# M8350.net
KiCad netlist of a schematic drawn in EAGLE
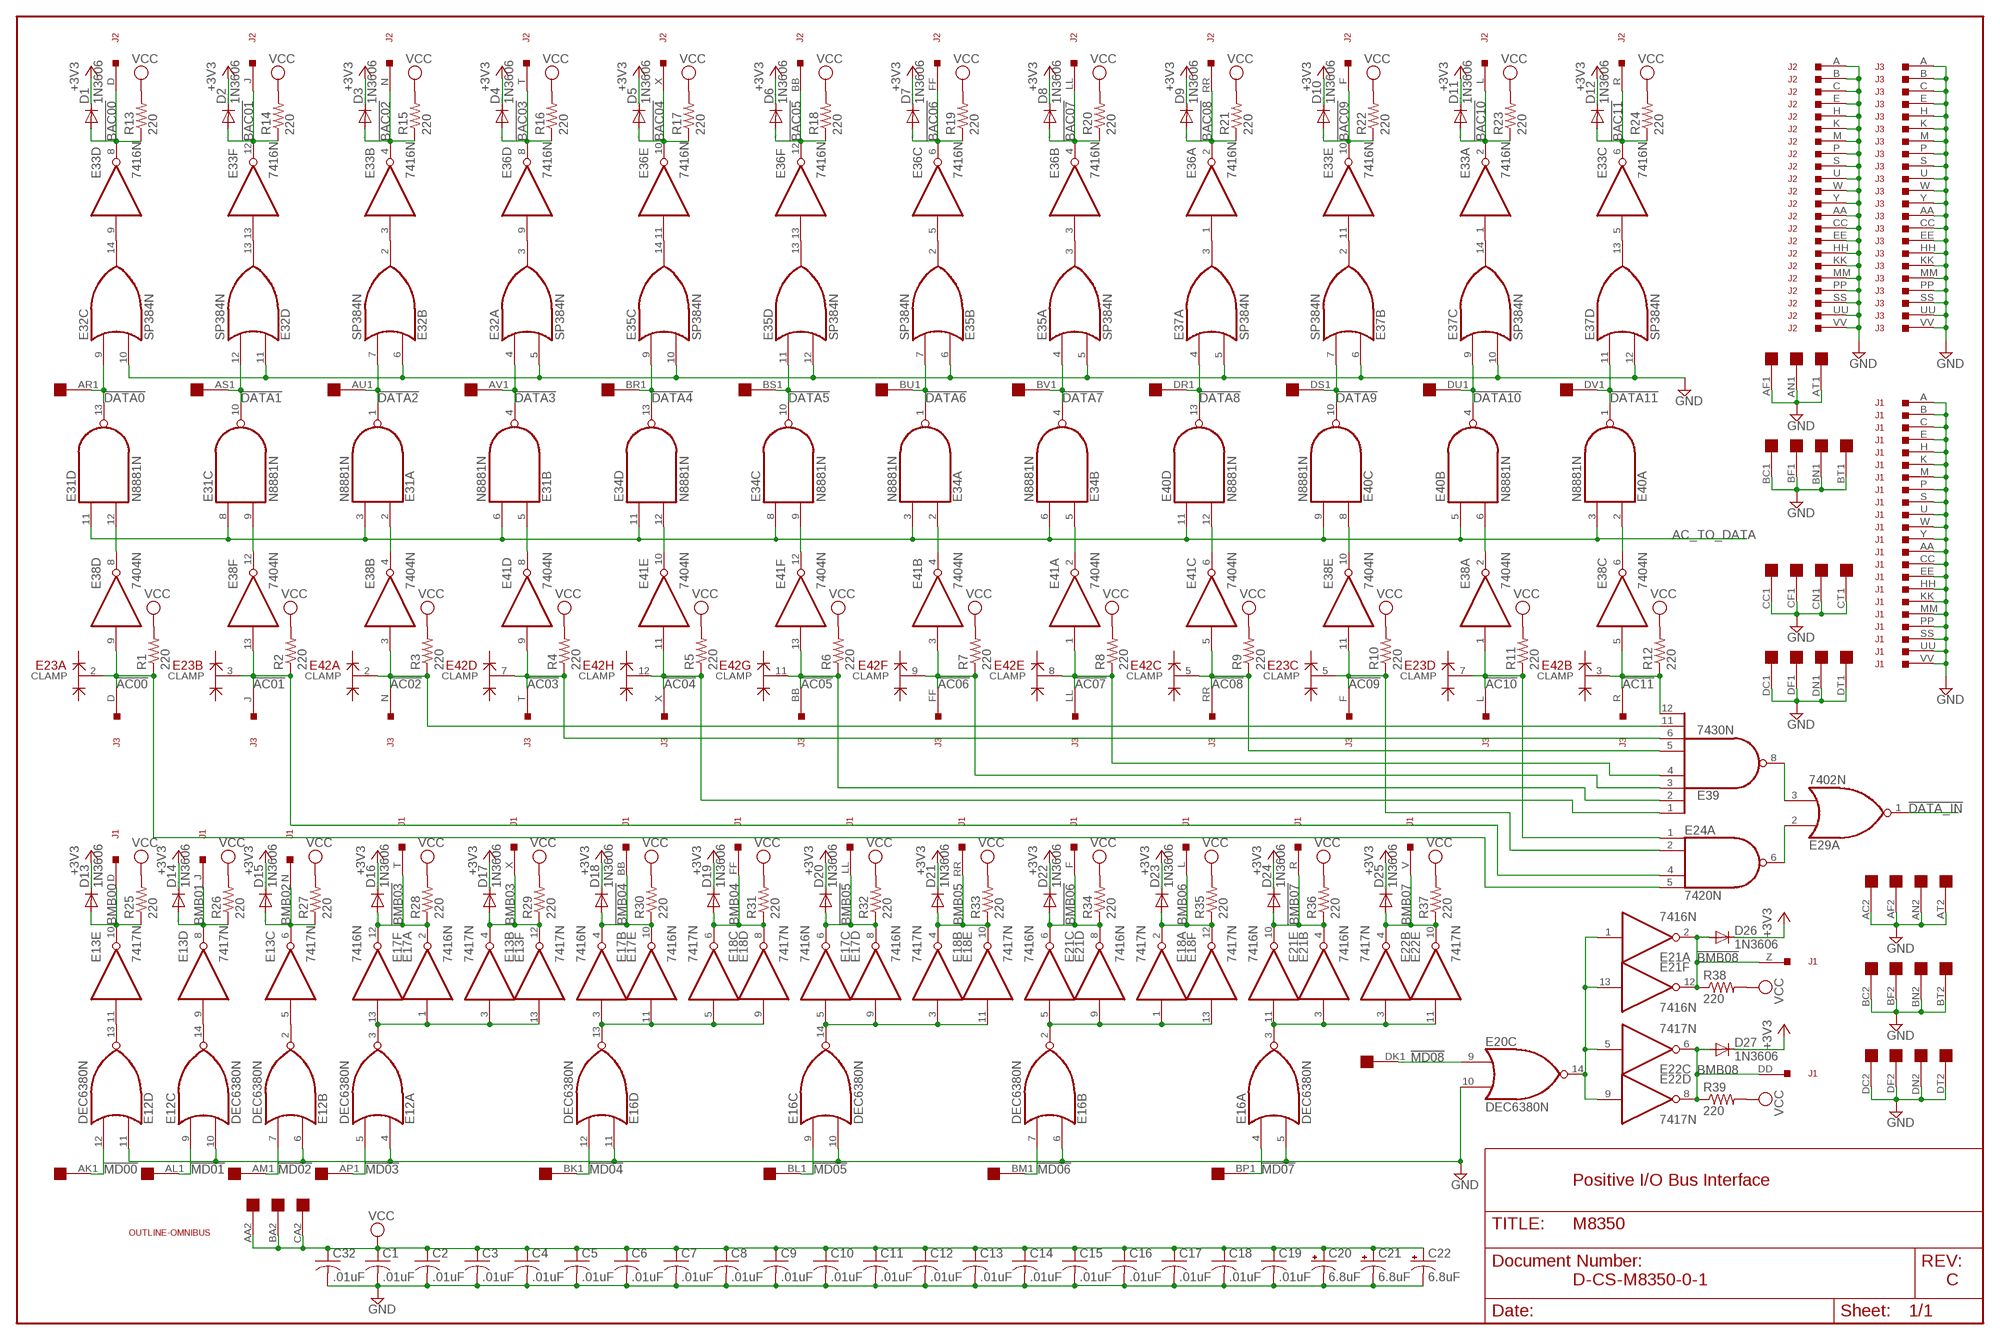
[diagram p0: schematic, sheet 1, part 1 of 2]
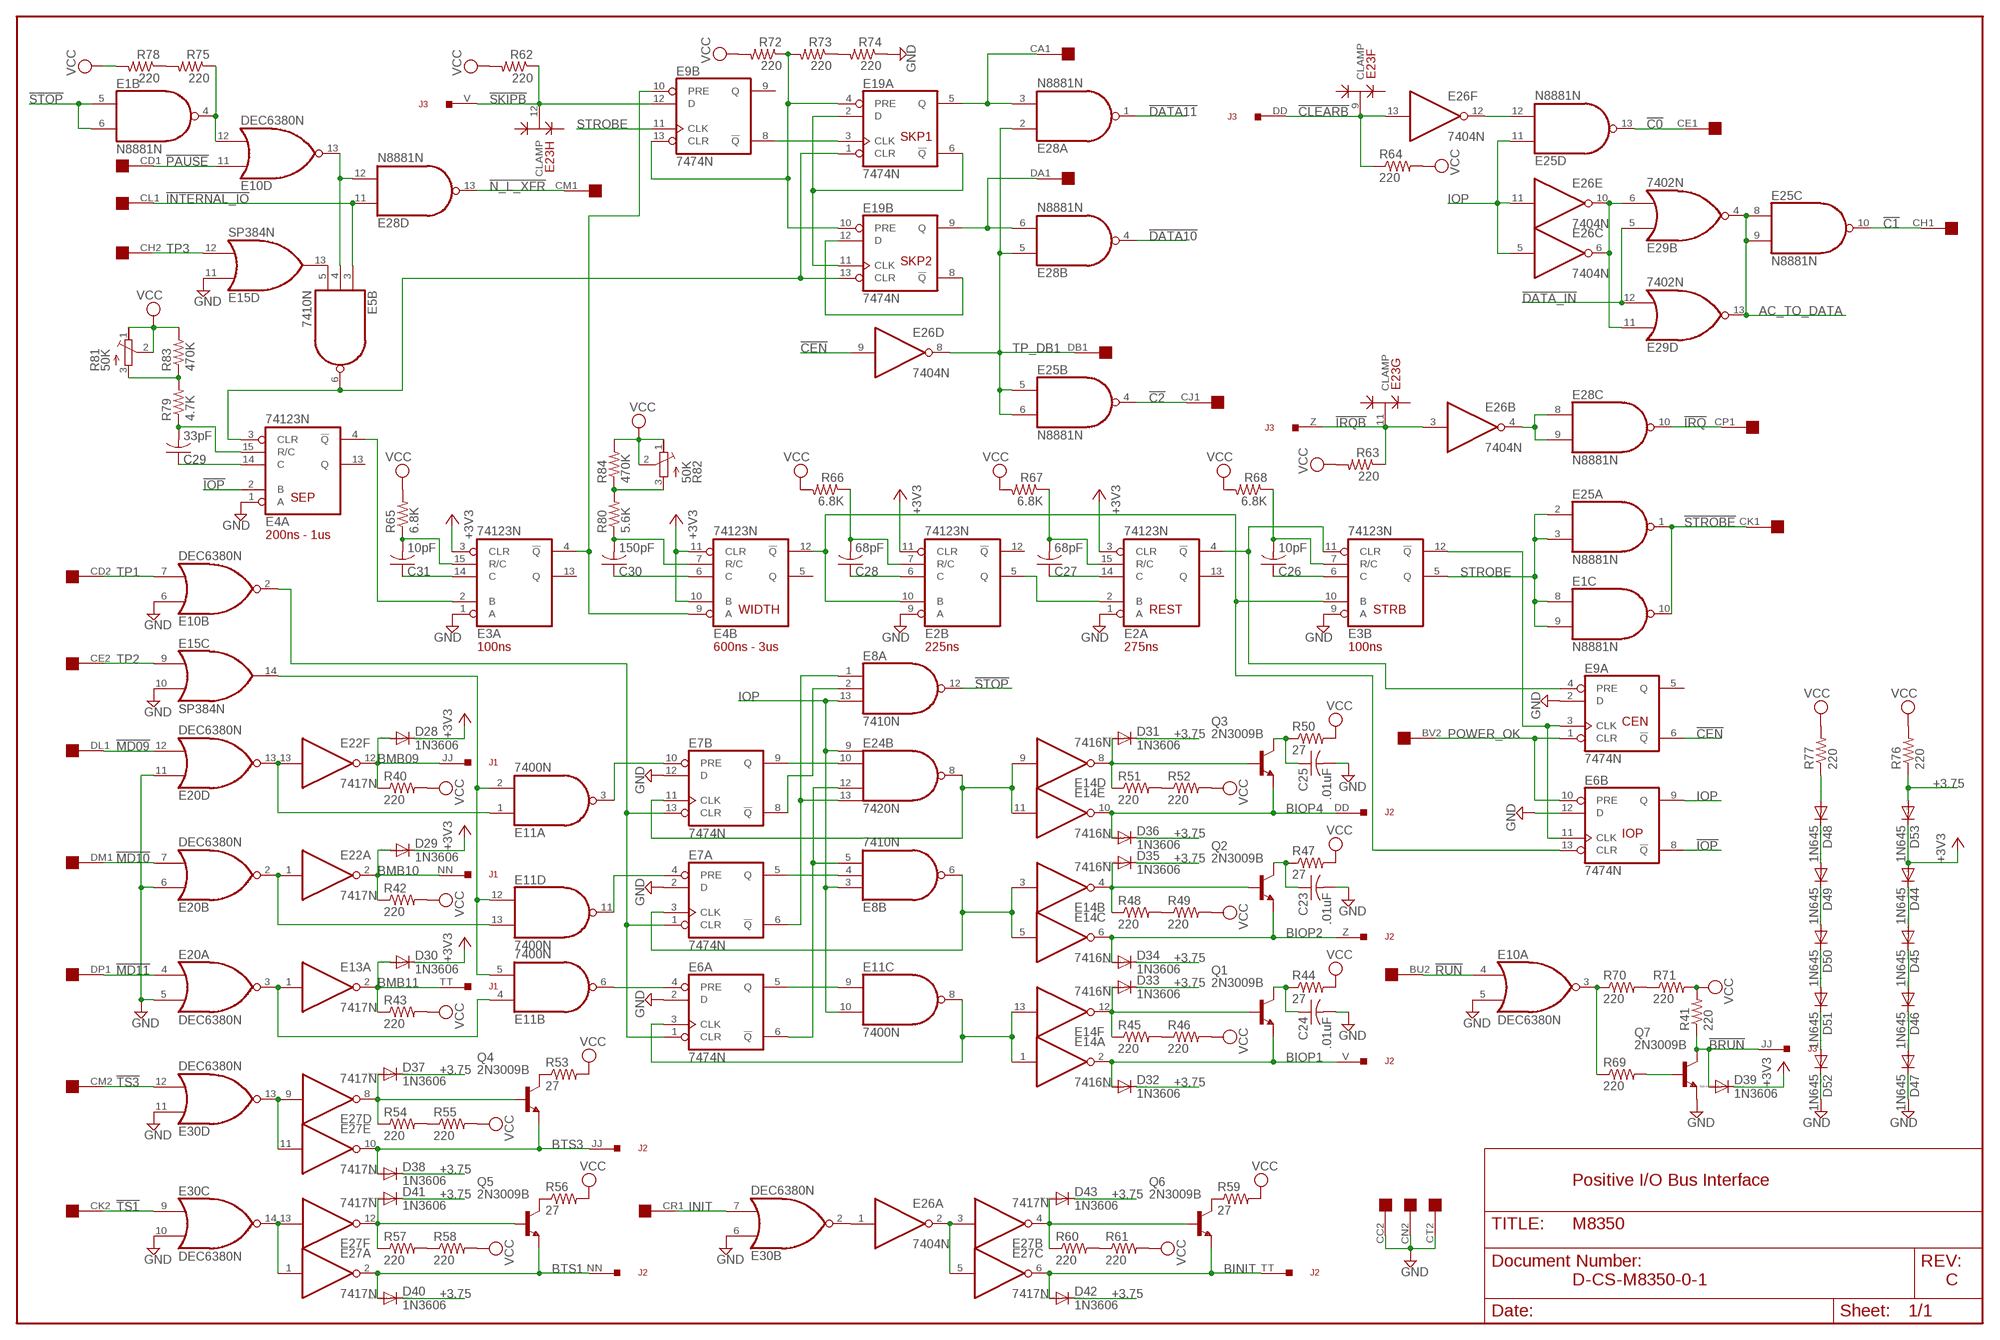
[diagram p1: schematic, sheet 1, part 2 of 2]

(export (version "E")
  (design (tool "Eeschema 10.0.6"))
  (components
    (comp (ref "C1")
      (value ".01uF")
      (footprint "eagle-import:C050-025X075")
      (libsource (lib "eagle-import") (part "C-US050-025X075"))
    )
    (comp (ref "C2")
      (value ".01uF")
      (footprint "eagle-import:C050-025X075")
      (libsource (lib "eagle-import") (part "C-US050-025X075"))
    )
    (comp (ref "C3")
      (value ".01uF")
      (footprint "eagle-import:C050-025X075")
      (libsource (lib "eagle-import") (part "C-US050-025X075"))
    )
    (comp (ref "C4")
      (value ".01uF")
      (footprint "eagle-import:C050-025X075")
      (libsource (lib "eagle-import") (part "C-US050-025X075"))
    )
    (comp (ref "C5")
      (value ".01uF")
      (footprint "eagle-import:C050-025X075")
      (libsource (lib "eagle-import") (part "C-US050-025X075"))
    )
    (comp (ref "C6")
      (value ".01uF")
      (footprint "eagle-import:C050-025X075")
      (libsource (lib "eagle-import") (part "C-US050-025X075"))
    )
    (comp (ref "C7")
      (value ".01uF")
      (footprint "eagle-import:C050-025X075")
      (libsource (lib "eagle-import") (part "C-US050-025X075"))
    )
    (comp (ref "C8")
      (value ".01uF")
      (footprint "eagle-import:C050-025X075")
      (libsource (lib "eagle-import") (part "C-US050-025X075"))
    )
    (comp (ref "C9")
      (value ".01uF")
      (footprint "eagle-import:C050-025X075")
      (libsource (lib "eagle-import") (part "C-US050-025X075"))
    )
    (comp (ref "C10")
      (value ".01uF")
      (footprint "eagle-import:C050-025X075")
      (libsource (lib "eagle-import") (part "C-US050-025X075"))
    )
    (comp (ref "C11")
      (value ".01uF")
      (footprint "eagle-import:C050-025X075")
      (libsource (lib "eagle-import") (part "C-US050-025X075"))
    )
    (comp (ref "C12")
      (value ".01uF")
      (footprint "eagle-import:C050-025X075")
      (libsource (lib "eagle-import") (part "C-US050-025X075"))
    )
    (comp (ref "C13")
      (value ".01uF")
      (footprint "eagle-import:C050-025X075")
      (libsource (lib "eagle-import") (part "C-US050-025X075"))
    )
    (comp (ref "C14")
      (value ".01uF")
      (footprint "eagle-import:C050-025X075")
      (libsource (lib "eagle-import") (part "C-US050-025X075"))
    )
    (comp (ref "C15")
      (value ".01uF")
      (footprint "eagle-import:C050-025X075")
      (libsource (lib "eagle-import") (part "C-US050-025X075"))
    )
    (comp (ref "C16")
      (value ".01uF")
      (footprint "eagle-import:C050-025X075")
      (libsource (lib "eagle-import") (part "C-US050-025X075"))
    )
    (comp (ref "C17")
      (value ".01uF")
      (footprint "eagle-import:C050-025X075")
      (libsource (lib "eagle-import") (part "C-US050-025X075"))
    )
    (comp (ref "C18")
      (value ".01uF")
      (footprint "eagle-import:C050-025X075")
      (libsource (lib "eagle-import") (part "C-US050-025X075"))
    )
    (comp (ref "C19")
      (value ".01uF")
      (footprint "eagle-import:C050-025X075")
      (libsource (lib "eagle-import") (part "C-US050-025X075"))
    )
    (comp (ref "C20")
      (value "6.8uF")
      (footprint "eagle-import:E12-8")
      (libsource (lib "eagle-import") (part "CPOL-USE20-8AXIAL"))
    )
    (comp (ref "C21")
      (value "6.8uF")
      (footprint "eagle-import:E12-8")
      (libsource (lib "eagle-import") (part "CPOL-USE20-8AXIAL"))
    )
    (comp (ref "C22")
      (value "6.8uF")
      (footprint "eagle-import:E12-8")
      (libsource (lib "eagle-import") (part "CPOL-USE20-8AXIAL"))
    )
    (comp (ref "C23")
      (value ".01uF")
      (footprint "eagle-import:C050-025X075")
      (libsource (lib "eagle-import") (part "C-US050-025X075"))
    )
    (comp (ref "C24")
      (value ".01uF")
      (footprint "eagle-import:C050-025X075")
      (libsource (lib "eagle-import") (part "C-US050-025X075"))
    )
    (comp (ref "C25")
      (value ".01uF")
      (footprint "eagle-import:C050-025X075")
      (libsource (lib "eagle-import") (part "C-US050-025X075"))
    )
    (comp (ref "C26")
      (value "10pF")
      (footprint "eagle-import:C050-025X075")
      (libsource (lib "eagle-import") (part "C-US050-025X075"))
    )
    (comp (ref "C27")
      (value "68pF")
      (footprint "eagle-import:C050-025X075")
      (libsource (lib "eagle-import") (part "C-US050-025X075"))
    )
    (comp (ref "C28")
      (value "68pF")
      (footprint "eagle-import:C050-025X075")
      (libsource (lib "eagle-import") (part "C-US050-025X075"))
    )
    (comp (ref "C29")
      (value "33pF")
      (footprint "eagle-import:C050-025X075")
      (libsource (lib "eagle-import") (part "C-US050-025X075"))
    )
    (comp (ref "C30")
      (value "150pF")
      (footprint "eagle-import:C050-025X075")
      (libsource (lib "eagle-import") (part "C-US050-025X075"))
    )
    (comp (ref "C31")
      (value "10pF")
      (footprint "eagle-import:C050-025X075")
      (libsource (lib "eagle-import") (part "C-US050-025X075"))
    )
    (comp (ref "C32")
      (value ".01uF")
      (footprint "eagle-import:C050-025X075")
      (libsource (lib "eagle-import") (part "C-US050-025X075"))
    )
    (comp (ref "D1")
      (value "1N3606")
      (footprint "eagle-import:DO35-10")
      (libsource (lib "eagle-import") (part "DIODE-DO35-10"))
    )
    (comp (ref "D2")
      (value "1N3606")
      (footprint "eagle-import:DO35-10")
      (libsource (lib "eagle-import") (part "DIODE-DO35-10"))
    )
    (comp (ref "D3")
      (value "1N3606")
      (footprint "eagle-import:DO35-10")
      (libsource (lib "eagle-import") (part "DIODE-DO35-10"))
    )
    (comp (ref "D4")
      (value "1N3606")
      (footprint "eagle-import:DO35-10")
      (libsource (lib "eagle-import") (part "DIODE-DO35-10"))
    )
    (comp (ref "D5")
      (value "1N3606")
      (footprint "eagle-import:DO35-10")
      (libsource (lib "eagle-import") (part "DIODE-DO35-10"))
    )
    (comp (ref "D6")
      (value "1N3606")
      (footprint "eagle-import:DO35-10")
      (libsource (lib "eagle-import") (part "DIODE-DO35-10"))
    )
    (comp (ref "D7")
      (value "1N3606")
      (footprint "eagle-import:DO35-10")
      (libsource (lib "eagle-import") (part "DIODE-DO35-10"))
    )
    (comp (ref "D8")
      (value "1N3606")
      (footprint "eagle-import:DO35-10")
      (libsource (lib "eagle-import") (part "DIODE-DO35-10"))
    )
    (comp (ref "D9")
      (value "1N3606")
      (footprint "eagle-import:DO35-10")
      (libsource (lib "eagle-import") (part "DIODE-DO35-10"))
    )
    (comp (ref "D10")
      (value "1N3606")
      (footprint "eagle-import:DO35-10")
      (libsource (lib "eagle-import") (part "DIODE-DO35-10"))
    )
    (comp (ref "D11")
      (value "1N3606")
      (footprint "eagle-import:DO35-10")
      (libsource (lib "eagle-import") (part "DIODE-DO35-10"))
    )
    (comp (ref "D12")
      (value "1N3606")
      (footprint "eagle-import:DO35-10")
      (libsource (lib "eagle-import") (part "DIODE-DO35-10"))
    )
    (comp (ref "D13")
      (value "1N3606")
      (footprint "eagle-import:DO35-10")
      (libsource (lib "eagle-import") (part "DIODE-DO35-10"))
    )
    (comp (ref "D14")
      (value "1N3606")
      (footprint "eagle-import:DO35-10")
      (libsource (lib "eagle-import") (part "DIODE-DO35-10"))
    )
    (comp (ref "D15")
      (value "1N3606")
      (footprint "eagle-import:DO35-10")
      (libsource (lib "eagle-import") (part "DIODE-DO35-10"))
    )
    (comp (ref "D16")
      (value "1N3606")
      (footprint "eagle-import:DO35-10")
      (libsource (lib "eagle-import") (part "DIODE-DO35-10"))
    )
    (comp (ref "D17")
      (value "1N3606")
      (footprint "eagle-import:DO35-10")
      (libsource (lib "eagle-import") (part "DIODE-DO35-10"))
    )
    (comp (ref "D18")
      (value "1N3606")
      (footprint "eagle-import:DO35-10")
      (libsource (lib "eagle-import") (part "DIODE-DO35-10"))
    )
    (comp (ref "D19")
      (value "1N3606")
      (footprint "eagle-import:DO35-10")
      (libsource (lib "eagle-import") (part "DIODE-DO35-10"))
    )
    (comp (ref "D20")
      (value "1N3606")
      (footprint "eagle-import:DO35-10")
      (libsource (lib "eagle-import") (part "DIODE-DO35-10"))
    )
    (comp (ref "D21")
      (value "1N3606")
      (footprint "eagle-import:DO35-10")
      (libsource (lib "eagle-import") (part "DIODE-DO35-10"))
    )
    (comp (ref "D22")
      (value "1N3606")
      (footprint "eagle-import:DO35-10")
      (libsource (lib "eagle-import") (part "DIODE-DO35-10"))
    )
    (comp (ref "D23")
      (value "1N3606")
      (footprint "eagle-import:DO35-10")
      (libsource (lib "eagle-import") (part "DIODE-DO35-10"))
    )
    (comp (ref "D24")
      (value "1N3606")
      (footprint "eagle-import:DO35-10")
      (libsource (lib "eagle-import") (part "DIODE-DO35-10"))
    )
    (comp (ref "D25")
      (value "1N3606")
      (footprint "eagle-import:DO35-10")
      (libsource (lib "eagle-import") (part "DIODE-DO35-10"))
    )
    (comp (ref "D26")
      (value "1N3606")
      (footprint "eagle-import:DO35-10")
      (libsource (lib "eagle-import") (part "DIODE-DO35-10"))
    )
    (comp (ref "D27")
      (value "1N3606")
      (footprint "eagle-import:DO35-10")
      (libsource (lib "eagle-import") (part "DIODE-DO35-10"))
    )
    (comp (ref "D28")
      (value "1N3606")
      (footprint "eagle-import:DO35-10")
      (libsource (lib "eagle-import") (part "DIODE-DO35-10"))
    )
    (comp (ref "D29")
      (value "1N3606")
      (footprint "eagle-import:DO35-10")
      (libsource (lib "eagle-import") (part "DIODE-DO35-10"))
    )
    (comp (ref "D30")
      (value "1N3606")
      (footprint "eagle-import:DO35-10")
      (libsource (lib "eagle-import") (part "DIODE-DO35-10"))
    )
    (comp (ref "D31")
      (value "1N3606")
      (footprint "eagle-import:DO35-10")
      (libsource (lib "eagle-import") (part "DIODE-DO35-10"))
    )
    (comp (ref "D32")
      (value "1N3606")
      (footprint "eagle-import:DO35-10")
      (libsource (lib "eagle-import") (part "DIODE-DO35-10"))
    )
    (comp (ref "D33")
      (value "1N3606")
      (footprint "eagle-import:DO35-10")
      (libsource (lib "eagle-import") (part "DIODE-DO35-10"))
    )
    (comp (ref "D34")
      (value "1N3606")
      (footprint "eagle-import:DO35-10")
      (libsource (lib "eagle-import") (part "DIODE-DO35-10"))
    )
    (comp (ref "D35")
      (value "1N3606")
      (footprint "eagle-import:DO35-10")
      (libsource (lib "eagle-import") (part "DIODE-DO35-10"))
    )
    (comp (ref "D36")
      (value "1N3606")
      (footprint "eagle-import:DO35-10")
      (libsource (lib "eagle-import") (part "DIODE-DO35-10"))
    )
    (comp (ref "D37")
      (value "1N3606")
      (footprint "eagle-import:DO35-10")
      (libsource (lib "eagle-import") (part "DIODE-DO35-10"))
    )
    (comp (ref "D38")
      (value "1N3606")
      (footprint "eagle-import:DO35-10")
      (libsource (lib "eagle-import") (part "DIODE-DO35-10"))
    )
    (comp (ref "D39")
      (value "1N3606")
      (footprint "eagle-import:DO35-10")
      (libsource (lib "eagle-import") (part "DIODE-DO35-10"))
    )
    (comp (ref "D40")
      (value "1N3606")
      (footprint "eagle-import:DO35-10")
      (libsource (lib "eagle-import") (part "DIODE-DO35-10"))
    )
    (comp (ref "D41")
      (value "1N3606")
      (footprint "eagle-import:DO35-10")
      (libsource (lib "eagle-import") (part "DIODE-DO35-10"))
    )
    (comp (ref "D42")
      (value "1N3606")
      (footprint "eagle-import:DO35-10")
      (libsource (lib "eagle-import") (part "DIODE-DO35-10"))
    )
    (comp (ref "D43")
      (value "1N3606")
      (footprint "eagle-import:DO35-10")
      (libsource (lib "eagle-import") (part "DIODE-DO35-10"))
    )
    (comp (ref "D44")
      (value "1N645")
      (footprint "eagle-import:DO35-10")
      (libsource (lib "eagle-import") (part "DIODE-DO35-10"))
    )
    (comp (ref "D45")
      (value "1N645")
      (footprint "eagle-import:DO35-10")
      (libsource (lib "eagle-import") (part "DIODE-DO35-10"))
    )
    (comp (ref "D46")
      (value "1N645")
      (footprint "eagle-import:DO35-10")
      (libsource (lib "eagle-import") (part "DIODE-DO35-10"))
    )
    (comp (ref "D47")
      (value "1N645")
      (footprint "eagle-import:DO35-10")
      (libsource (lib "eagle-import") (part "DIODE-DO35-10"))
    )
    (comp (ref "D48")
      (value "1N645")
      (footprint "eagle-import:DO35-10")
      (libsource (lib "eagle-import") (part "DIODE-DO35-10"))
    )
    (comp (ref "D49")
      (value "1N645")
      (footprint "eagle-import:DO35-10")
      (libsource (lib "eagle-import") (part "DIODE-DO35-10"))
    )
    (comp (ref "D50")
      (value "1N645")
      (footprint "eagle-import:DO35-10")
      (libsource (lib "eagle-import") (part "DIODE-DO35-10"))
    )
    (comp (ref "D51")
      (value "1N645")
      (footprint "eagle-import:DO35-10")
      (libsource (lib "eagle-import") (part "DIODE-DO35-10"))
    )
    (comp (ref "D52")
      (value "1N645")
      (footprint "eagle-import:DO35-10")
      (libsource (lib "eagle-import") (part "DIODE-DO35-10"))
    )
    (comp (ref "D53")
      (value "1N645")
      (footprint "eagle-import:DO35-10")
      (libsource (lib "eagle-import") (part "DIODE-DO35-10"))
    )
    (comp (ref "E1")
      (value "N8881N")
      (footprint "eagle-import:DIL14")
      (libsource (lib "eagle-import") (part "N8881N"))
    )
    (comp (ref "E2")
      (value "74123N")
      (footprint "eagle-import:DIL16")
      (libsource (lib "eagle-import") (part "74123N"))
    )
    (comp (ref "E3")
      (value "74123N")
      (footprint "eagle-import:DIL16")
      (libsource (lib "eagle-import") (part "74123N"))
    )
    (comp (ref "E4")
      (value "74123N")
      (footprint "eagle-import:DIL16")
      (libsource (lib "eagle-import") (part "74123N"))
    )
    (comp (ref "E5")
      (value "7410N")
      (footprint "eagle-import:DIL14")
      (libsource (lib "eagle-import") (part "7410N"))
    )
    (comp (ref "E6")
      (value "7474N")
      (footprint "eagle-import:DIL14")
      (libsource (lib "eagle-import") (part "7474NS"))
    )
    (comp (ref "E7")
      (value "7474N")
      (footprint "eagle-import:DIL14")
      (libsource (lib "eagle-import") (part "7474NS"))
    )
    (comp (ref "E8")
      (value "7410N")
      (footprint "eagle-import:DIL14")
      (libsource (lib "eagle-import") (part "7410N"))
    )
    (comp (ref "E9")
      (value "7474N")
      (footprint "eagle-import:DIL14")
      (libsource (lib "eagle-import") (part "7474NS"))
    )
    (comp (ref "E10")
      (value "DEC6380N")
      (footprint "eagle-import:DIL14")
      (libsource (lib "eagle-import") (part "SP380N"))
    )
    (comp (ref "E11")
      (value "7400N")
      (footprint "eagle-import:DIL14")
      (libsource (lib "eagle-import") (part "7400N"))
    )
    (comp (ref "E12")
      (value "DEC6380N")
      (footprint "eagle-import:DIL14")
      (libsource (lib "eagle-import") (part "SP380N"))
    )
    (comp (ref "E13")
      (value "7417N")
      (footprint "eagle-import:DIL14")
      (libsource (lib "eagle-import") (part "7417N"))
    )
    (comp (ref "E14")
      (value "7416N")
      (footprint "eagle-import:DIL14")
      (libsource (lib "eagle-import") (part "7416N"))
    )
    (comp (ref "E15")
      (value "SP384N")
      (footprint "eagle-import:DIL14")
      (libsource (lib "eagle-import") (part "SP384N"))
    )
    (comp (ref "E16")
      (value "DEC6380N")
      (footprint "eagle-import:DIL14")
      (libsource (lib "eagle-import") (part "SP380N"))
    )
    (comp (ref "E17")
      (value "7416N")
      (footprint "eagle-import:DIL14")
      (libsource (lib "eagle-import") (part "7416N"))
    )
    (comp (ref "E18")
      (value "7417N")
      (footprint "eagle-import:DIL14")
      (libsource (lib "eagle-import") (part "7417N"))
    )
    (comp (ref "E19")
      (value "7474N")
      (footprint "eagle-import:DIL14")
      (libsource (lib "eagle-import") (part "7474NS"))
    )
    (comp (ref "E20")
      (value "DEC6380N")
      (footprint "eagle-import:DIL14")
      (libsource (lib "eagle-import") (part "SP380N"))
    )
    (comp (ref "E21")
      (value "7416N")
      (footprint "eagle-import:DIL14")
      (libsource (lib "eagle-import") (part "7416N"))
    )
    (comp (ref "E22")
      (value "7417N")
      (footprint "eagle-import:DIL14")
      (libsource (lib "eagle-import") (part "7417N"))
    )
    (comp (ref "E23")
      (value "DEC2501")
      (footprint "eagle-import:DIL14")
      (libsource (lib "eagle-import") (part "DEC2501"))
    )
    (comp (ref "E24")
      (value "7420N")
      (footprint "eagle-import:DIL14")
      (libsource (lib "eagle-import") (part "7420NS"))
    )
    (comp (ref "E25")
      (value "N8881N")
      (footprint "eagle-import:DIL14")
      (libsource (lib "eagle-import") (part "N8881N"))
    )
    (comp (ref "E26")
      (value "7404N")
      (footprint "eagle-import:DIL14")
      (libsource (lib "eagle-import") (part "7404N"))
    )
    (comp (ref "E27")
      (value "7417N")
      (footprint "eagle-import:DIL14")
      (libsource (lib "eagle-import") (part "7417N"))
    )
    (comp (ref "E28")
      (value "N8881N")
      (footprint "eagle-import:DIL14")
      (libsource (lib "eagle-import") (part "N8881N"))
    )
    (comp (ref "E29")
      (value "7402N")
      (footprint "eagle-import:DIL14")
      (libsource (lib "eagle-import") (part "7402N"))
    )
    (comp (ref "E30")
      (value "DEC6380N")
      (footprint "eagle-import:DIL14")
      (libsource (lib "eagle-import") (part "SP380N"))
    )
    (comp (ref "E31")
      (value "N8881N")
      (footprint "eagle-import:DIL14")
      (libsource (lib "eagle-import") (part "N8881N"))
    )
    (comp (ref "E32")
      (value "SP384N")
      (footprint "eagle-import:DIL14")
      (libsource (lib "eagle-import") (part "SP384N"))
    )
    (comp (ref "E33")
      (value "7416N")
      (footprint "eagle-import:DIL14")
      (libsource (lib "eagle-import") (part "7416N"))
    )
    (comp (ref "E34")
      (value "N8881N")
      (footprint "eagle-import:DIL14")
      (libsource (lib "eagle-import") (part "N8881N"))
    )
    (comp (ref "E35")
      (value "SP384N")
      (footprint "eagle-import:DIL14")
      (libsource (lib "eagle-import") (part "SP384N"))
    )
    (comp (ref "E36")
      (value "7416N")
      (footprint "eagle-import:DIL14")
      (libsource (lib "eagle-import") (part "7416N"))
    )
    (comp (ref "E37")
      (value "SP384N")
      (footprint "eagle-import:DIL14")
      (libsource (lib "eagle-import") (part "SP384N"))
    )
    (comp (ref "E38")
      (value "7404N")
      (footprint "eagle-import:DIL14")
      (libsource (lib "eagle-import") (part "7404N"))
    )
    (comp (ref "E39")
      (value "7430N")
      (footprint "eagle-import:DIL14")
      (libsource (lib "eagle-import") (part "7430N"))
    )
    (comp (ref "E40")
      (value "N8881N")
      (footprint "eagle-import:DIL14")
      (libsource (lib "eagle-import") (part "N8881N"))
    )
    (comp (ref "E41")
      (value "7404N")
      (footprint "eagle-import:DIL14")
      (libsource (lib "eagle-import") (part "7404N"))
    )
    (comp (ref "E42")
      (value "DEC2501")
      (footprint "eagle-import:DIL14")
      (libsource (lib "eagle-import") (part "DEC2501"))
    )
    (comp (ref "J1")
      (value "DEC40PINSH")
      (footprint "eagle-import:DEC40PINH")
      (libsource (lib "eagle-import") (part "DEC40PINSH"))
    )
    (comp (ref "J2")
      (value "DEC40PINSH")
      (footprint "eagle-import:DEC40PINH")
      (libsource (lib "eagle-import") (part "DEC40PINSH"))
    )
    (comp (ref "J3")
      (value "DEC40PINSH")
      (footprint "eagle-import:DEC40PINH")
      (libsource (lib "eagle-import") (part "DEC40PINSH"))
    )
    (comp (ref "Q1")
      (value "2N3009B")
      (footprint "eagle-import:TO5")
      (libsource (lib "eagle-import") (part "-NPN-TO5"))
    )
    (comp (ref "Q2")
      (value "2N3009B")
      (footprint "eagle-import:TO5")
      (libsource (lib "eagle-import") (part "-NPN-TO5"))
    )
    (comp (ref "Q3")
      (value "2N3009B")
      (footprint "eagle-import:TO5")
      (libsource (lib "eagle-import") (part "-NPN-TO5"))
    )
    (comp (ref "Q4")
      (value "2N3009B")
      (footprint "eagle-import:TO5")
      (libsource (lib "eagle-import") (part "-NPN-TO5"))
    )
    (comp (ref "Q5")
      (value "2N3009B")
      (footprint "eagle-import:TO5")
      (libsource (lib "eagle-import") (part "-NPN-TO5"))
    )
    (comp (ref "Q6")
      (value "2N3009B")
      (footprint "eagle-import:TO5")
      (libsource (lib "eagle-import") (part "-NPN-TO5"))
    )
    (comp (ref "Q7")
      (value "2N3009B")
      (footprint "eagle-import:TO5")
      (libsource (lib "eagle-import") (part "-NPN-TO5"))
    )
    (comp (ref "R1")
      (value "220")
      (footprint "eagle-import:0207_10")
      (libsource (lib "eagle-import") (part "R-US_0207/10"))
    )
    (comp (ref "R2")
      (value "220")
      (footprint "eagle-import:0207_10")
      (libsource (lib "eagle-import") (part "R-US_0207/10"))
    )
    (comp (ref "R3")
      (value "220")
      (footprint "eagle-import:0207_10")
      (libsource (lib "eagle-import") (part "R-US_0207/10"))
    )
    (comp (ref "R4")
      (value "220")
      (footprint "eagle-import:0207_10")
      (libsource (lib "eagle-import") (part "R-US_0207/10"))
    )
    (comp (ref "R5")
      (value "220")
      (footprint "eagle-import:0207_10")
      (libsource (lib "eagle-import") (part "R-US_0207/10"))
    )
    (comp (ref "R6")
      (value "220")
      (footprint "eagle-import:0207_10")
      (libsource (lib "eagle-import") (part "R-US_0207/10"))
    )
    (comp (ref "R7")
      (value "220")
      (footprint "eagle-import:0207_10")
      (libsource (lib "eagle-import") (part "R-US_0207/10"))
    )
    (comp (ref "R8")
      (value "220")
      (footprint "eagle-import:0207_10")
      (libsource (lib "eagle-import") (part "R-US_0207/10"))
    )
    (comp (ref "R9")
      (value "220")
      (footprint "eagle-import:0207_10")
      (libsource (lib "eagle-import") (part "R-US_0207/10"))
    )
    (comp (ref "R10")
      (value "220")
      (footprint "eagle-import:0207_10")
      (libsource (lib "eagle-import") (part "R-US_0207/10"))
    )
    (comp (ref "R11")
      (value "220")
      (footprint "eagle-import:0207_10")
      (libsource (lib "eagle-import") (part "R-US_0207/10"))
    )
    (comp (ref "R12")
      (value "220")
      (footprint "eagle-import:0207_10")
      (libsource (lib "eagle-import") (part "R-US_0207/10"))
    )
    (comp (ref "R13")
      (value "220")
      (footprint "eagle-import:0207_10")
      (libsource (lib "eagle-import") (part "R-US_0207/10"))
    )
    (comp (ref "R14")
      (value "220")
      (footprint "eagle-import:0207_10")
      (libsource (lib "eagle-import") (part "R-US_0207/10"))
    )
    (comp (ref "R15")
      (value "220")
      (footprint "eagle-import:0207_10")
      (libsource (lib "eagle-import") (part "R-US_0207/10"))
    )
    (comp (ref "R16")
      (value "220")
      (footprint "eagle-import:0207_10")
      (libsource (lib "eagle-import") (part "R-US_0207/10"))
    )
    (comp (ref "R17")
      (value "220")
      (footprint "eagle-import:0207_10")
      (libsource (lib "eagle-import") (part "R-US_0207/10"))
    )
    (comp (ref "R18")
      (value "220")
      (footprint "eagle-import:0207_10")
      (libsource (lib "eagle-import") (part "R-US_0207/10"))
    )
    (comp (ref "R19")
      (value "220")
      (footprint "eagle-import:0207_10")
      (libsource (lib "eagle-import") (part "R-US_0207/10"))
    )
    (comp (ref "R20")
      (value "220")
      (footprint "eagle-import:0207_10")
      (libsource (lib "eagle-import") (part "R-US_0207/10"))
    )
    (comp (ref "R21")
      (value "220")
      (footprint "eagle-import:0207_10")
      (libsource (lib "eagle-import") (part "R-US_0207/10"))
    )
    (comp (ref "R22")
      (value "220")
      (footprint "eagle-import:0207_10")
      (libsource (lib "eagle-import") (part "R-US_0207/10"))
    )
    (comp (ref "R23")
      (value "220")
      (footprint "eagle-import:0207_10")
      (libsource (lib "eagle-import") (part "R-US_0207/10"))
    )
    (comp (ref "R24")
      (value "220")
      (footprint "eagle-import:0207_10")
      (libsource (lib "eagle-import") (part "R-US_0207/10"))
    )
    (comp (ref "R25")
      (value "220")
      (footprint "eagle-import:0207_10")
      (libsource (lib "eagle-import") (part "R-US_0207/10"))
    )
    (comp (ref "R26")
      (value "220")
      (footprint "eagle-import:0207_10")
      (libsource (lib "eagle-import") (part "R-US_0207/10"))
    )
    (comp (ref "R27")
      (value "220")
      (footprint "eagle-import:0207_10")
      (libsource (lib "eagle-import") (part "R-US_0207/10"))
    )
    (comp (ref "R28")
      (value "220")
      (footprint "eagle-import:0207_10")
      (libsource (lib "eagle-import") (part "R-US_0207/10"))
    )
    (comp (ref "R29")
      (value "220")
      (footprint "eagle-import:0207_10")
      (libsource (lib "eagle-import") (part "R-US_0207/10"))
    )
    (comp (ref "R30")
      (value "220")
      (footprint "eagle-import:0207_10")
      (libsource (lib "eagle-import") (part "R-US_0207/10"))
    )
    (comp (ref "R31")
      (value "220")
      (footprint "eagle-import:0207_10")
      (libsource (lib "eagle-import") (part "R-US_0207/10"))
    )
    (comp (ref "R32")
      (value "220")
      (footprint "eagle-import:0207_10")
      (libsource (lib "eagle-import") (part "R-US_0207/10"))
    )
    (comp (ref "R33")
      (value "220")
      (footprint "eagle-import:0207_10")
      (libsource (lib "eagle-import") (part "R-US_0207/10"))
    )
    (comp (ref "R34")
      (value "220")
      (footprint "eagle-import:0207_10")
      (libsource (lib "eagle-import") (part "R-US_0207/10"))
    )
    (comp (ref "R35")
      (value "220")
      (footprint "eagle-import:0207_10")
      (libsource (lib "eagle-import") (part "R-US_0207/10"))
    )
    (comp (ref "R36")
      (value "220")
      (footprint "eagle-import:0207_10")
      (libsource (lib "eagle-import") (part "R-US_0207/10"))
    )
    (comp (ref "R37")
      (value "220")
      (footprint "eagle-import:0207_10")
      (libsource (lib "eagle-import") (part "R-US_0207/10"))
    )
    (comp (ref "R38")
      (value "220")
      (footprint "eagle-import:0207_10")
      (libsource (lib "eagle-import") (part "R-US_0207/10"))
    )
    (comp (ref "R39")
      (value "220")
      (footprint "eagle-import:0207_10")
      (libsource (lib "eagle-import") (part "R-US_0207/10"))
    )
    (comp (ref "R40")
      (value "220")
      (footprint "eagle-import:0207_10")
      (libsource (lib "eagle-import") (part "R-US_0207/10"))
    )
    (comp (ref "R41")
      (value "220")
      (footprint "eagle-import:0207_10")
      (libsource (lib "eagle-import") (part "R-US_0207/10"))
    )
    (comp (ref "R42")
      (value "220")
      (footprint "eagle-import:0207_10")
      (libsource (lib "eagle-import") (part "R-US_0207/10"))
    )
    (comp (ref "R43")
      (value "220")
      (footprint "eagle-import:0207_10")
      (libsource (lib "eagle-import") (part "R-US_0207/10"))
    )
    (comp (ref "R44")
      (value "27")
      (footprint "eagle-import:0207_10")
      (libsource (lib "eagle-import") (part "R-US_0207/10"))
    )
    (comp (ref "R45")
      (value "220")
      (footprint "eagle-import:0207_10")
      (libsource (lib "eagle-import") (part "R-US_0207/10"))
    )
    (comp (ref "R46")
      (value "220")
      (footprint "eagle-import:0207_10")
      (libsource (lib "eagle-import") (part "R-US_0207/10"))
    )
    (comp (ref "R47")
      (value "27")
      (footprint "eagle-import:0207_10")
      (libsource (lib "eagle-import") (part "R-US_0207/10"))
    )
    (comp (ref "R48")
      (value "220")
      (footprint "eagle-import:0207_10")
      (libsource (lib "eagle-import") (part "R-US_0207/10"))
    )
    (comp (ref "R49")
      (value "220")
      (footprint "eagle-import:0207_10")
      (libsource (lib "eagle-import") (part "R-US_0207/10"))
    )
    (comp (ref "R50")
      (value "27")
      (footprint "eagle-import:0207_10")
      (libsource (lib "eagle-import") (part "R-US_0207/10"))
    )
    (comp (ref "R51")
      (value "220")
      (footprint "eagle-import:0207_10")
      (libsource (lib "eagle-import") (part "R-US_0207/10"))
    )
    (comp (ref "R52")
      (value "220")
      (footprint "eagle-import:0207_10")
      (libsource (lib "eagle-import") (part "R-US_0207/10"))
    )
    (comp (ref "R53")
      (value "27")
      (footprint "eagle-import:0207_10")
      (libsource (lib "eagle-import") (part "R-US_0207/10"))
    )
    (comp (ref "R54")
      (value "220")
      (footprint "eagle-import:0207_10")
      (libsource (lib "eagle-import") (part "R-US_0207/10"))
    )
    (comp (ref "R55")
      (value "220")
      (footprint "eagle-import:0207_10")
      (libsource (lib "eagle-import") (part "R-US_0207/10"))
    )
    (comp (ref "R56")
      (value "27")
      (footprint "eagle-import:0207_10")
      (libsource (lib "eagle-import") (part "R-US_0207/10"))
    )
    (comp (ref "R57")
      (value "220")
      (footprint "eagle-import:0207_10")
      (libsource (lib "eagle-import") (part "R-US_0207/10"))
    )
    (comp (ref "R58")
      (value "220")
      (footprint "eagle-import:0207_10")
      (libsource (lib "eagle-import") (part "R-US_0207/10"))
    )
    (comp (ref "R59")
      (value "27")
      (footprint "eagle-import:0207_10")
      (libsource (lib "eagle-import") (part "R-US_0207/10"))
    )
    (comp (ref "R60")
      (value "220")
      (footprint "eagle-import:0207_10")
      (libsource (lib "eagle-import") (part "R-US_0207/10"))
    )
    (comp (ref "R61")
      (value "220")
      (footprint "eagle-import:0207_10")
      (libsource (lib "eagle-import") (part "R-US_0207/10"))
    )
    (comp (ref "R62")
      (value "220")
      (footprint "eagle-import:0207_10")
      (libsource (lib "eagle-import") (part "R-US_0207/10"))
    )
    (comp (ref "R63")
      (value "220")
      (footprint "eagle-import:0207_10")
      (libsource (lib "eagle-import") (part "R-US_0207/10"))
    )
    (comp (ref "R64")
      (value "220")
      (footprint "eagle-import:0207_10")
      (libsource (lib "eagle-import") (part "R-US_0207/10"))
    )
    (comp (ref "R65")
      (value "6.8K")
      (footprint "eagle-import:0207_10")
      (libsource (lib "eagle-import") (part "R-US_0207/10"))
    )
    (comp (ref "R66")
      (value "6.8K")
      (footprint "eagle-import:0207_10")
      (libsource (lib "eagle-import") (part "R-US_0207/10"))
    )
    (comp (ref "R67")
      (value "6.8K")
      (footprint "eagle-import:0207_10")
      (libsource (lib "eagle-import") (part "R-US_0207/10"))
    )
    (comp (ref "R68")
      (value "6.8K")
      (footprint "eagle-import:0207_10")
      (libsource (lib "eagle-import") (part "R-US_0207/10"))
    )
    (comp (ref "R69")
      (value "220")
      (footprint "eagle-import:0207_10")
      (libsource (lib "eagle-import") (part "R-US_0207/10"))
    )
    (comp (ref "R70")
      (value "220")
      (footprint "eagle-import:0207_10")
      (libsource (lib "eagle-import") (part "R-US_0207/10"))
    )
    (comp (ref "R71")
      (value "220")
      (footprint "eagle-import:0207_10")
      (libsource (lib "eagle-import") (part "R-US_0207/10"))
    )
    (comp (ref "R72")
      (value "220")
      (footprint "eagle-import:0207_10")
      (libsource (lib "eagle-import") (part "R-US_0207/10"))
    )
    (comp (ref "R73")
      (value "220")
      (footprint "eagle-import:0207_10")
      (libsource (lib "eagle-import") (part "R-US_0207/10"))
    )
    (comp (ref "R74")
      (value "220")
      (footprint "eagle-import:0207_10")
      (libsource (lib "eagle-import") (part "R-US_0207/10"))
    )
    (comp (ref "R75")
      (value "220")
      (footprint "eagle-import:0207_10")
      (libsource (lib "eagle-import") (part "R-US_0207/10"))
    )
    (comp (ref "R76")
      (value "220")
      (footprint "eagle-import:0207_10")
      (libsource (lib "eagle-import") (part "R-US_0207/10"))
    )
    (comp (ref "R77")
      (value "220")
      (footprint "eagle-import:0207_10")
      (libsource (lib "eagle-import") (part "R-US_0207/10"))
    )
    (comp (ref "R78")
      (value "220")
      (footprint "eagle-import:0207_10")
      (libsource (lib "eagle-import") (part "R-US_0207/10"))
    )
    (comp (ref "R79")
      (value "4.7K")
      (footprint "eagle-import:0207_10")
      (libsource (lib "eagle-import") (part "R-US_0207/10"))
    )
    (comp (ref "R80")
      (value "5.6K")
      (footprint "eagle-import:0207_10")
      (libsource (lib "eagle-import") (part "R-US_0207/10"))
    )
    (comp (ref "R81")
      (value "50K")
      (footprint "eagle-import:3006Y")
      (libsource (lib "eagle-import") (part "275P"))
    )
    (comp (ref "R82")
      (value "50K")
      (footprint "eagle-import:3006Y")
      (libsource (lib "eagle-import") (part "275P"))
    )
    (comp (ref "R83")
      (value "470K")
      (footprint "eagle-import:0207_10")
      (libsource (lib "eagle-import") (part "R-US_0207/10"))
    )
    (comp (ref "R84")
      (value "470K")
      (footprint "eagle-import:0207_10")
      (libsource (lib "eagle-import") (part "R-US_0207/10"))
    )
    (comp (ref "U$1")
      (value "OUTLINE-OMNIBUS")
      (footprint "eagle-import:OMNIBUS")
      (libsource (lib "eagle-import") (part "OUTLINE-OMNIBUS"))
    )
    (comp (ref "U$2")
      (value "QUAD")
      (footprint "eagle-import:EDGE-CON8")
      (libsource (lib "eagle-import") (part "QUAD"))
    )
  )
  (nets
    (net (code "1") (name "+3V3") (class "Default")
      (node (ref "D1") (pin "C") (pinfunction "C_C") (pintype "passive"))
      (node (ref "D10") (pin "C") (pinfunction "C_C") (pintype "passive"))
      (node (ref "D11") (pin "C") (pinfunction "C_C") (pintype "passive"))
      (node (ref "D12") (pin "C") (pinfunction "C_C") (pintype "passive"))
      (node (ref "D13") (pin "C") (pinfunction "C_C") (pintype "passive"))
      (node (ref "D14") (pin "C") (pinfunction "C_C") (pintype "passive"))
      (node (ref "D15") (pin "C") (pinfunction "C_C") (pintype "passive"))
      (node (ref "D16") (pin "C") (pinfunction "C_C") (pintype "passive"))
      (node (ref "D17") (pin "C") (pinfunction "C_C") (pintype "passive"))
      (node (ref "D18") (pin "C") (pinfunction "C_C") (pintype "passive"))
      (node (ref "D19") (pin "C") (pinfunction "C_C") (pintype "passive"))
      (node (ref "D2") (pin "C") (pinfunction "C_C") (pintype "passive"))
      (node (ref "D20") (pin "C") (pinfunction "C_C") (pintype "passive"))
      (node (ref "D21") (pin "C") (pinfunction "C_C") (pintype "passive"))
      (node (ref "D22") (pin "C") (pinfunction "C_C") (pintype "passive"))
      (node (ref "D23") (pin "C") (pinfunction "C_C") (pintype "passive"))
      (node (ref "D24") (pin "C") (pinfunction "C_C") (pintype "passive"))
      (node (ref "D25") (pin "C") (pinfunction "C_C") (pintype "passive"))
      (node (ref "D26") (pin "C") (pinfunction "C_C") (pintype "passive"))
      (node (ref "D27") (pin "C") (pinfunction "C_C") (pintype "passive"))
      (node (ref "D28") (pin "C") (pinfunction "C_C") (pintype "passive"))
      (node (ref "D29") (pin "C") (pinfunction "C_C") (pintype "passive"))
      (node (ref "D3") (pin "C") (pinfunction "C_C") (pintype "passive"))
      (node (ref "D30") (pin "C") (pinfunction "C_C") (pintype "passive"))
      (node (ref "D39") (pin "C") (pinfunction "C_C") (pintype "passive"))
      (node (ref "D4") (pin "C") (pinfunction "C_C") (pintype "passive"))
      (node (ref "D44") (pin "A") (pinfunction "A_A") (pintype "passive"))
      (node (ref "D5") (pin "C") (pinfunction "C_C") (pintype "passive"))
      (node (ref "D53") (pin "C") (pinfunction "C_C") (pintype "passive"))
      (node (ref "D6") (pin "C") (pinfunction "C_C") (pintype "passive"))
      (node (ref "D7") (pin "C") (pinfunction "C_C") (pintype "passive"))
      (node (ref "D8") (pin "C") (pinfunction "C_C") (pintype "passive"))
      (node (ref "D9") (pin "C") (pinfunction "C_C") (pintype "passive"))
      (node (ref "E2") (pin "11") (pinfunction "CLR_11") (pintype "input"))
      (node (ref "E2") (pin "3") (pinfunction "CLR_3") (pintype "input"))
      (node (ref "E3") (pin "3") (pinfunction "CLR_3") (pintype "input"))
      (node (ref "E4") (pin "10") (pinfunction "B_10") (pintype "input"))
      (node (ref "E4") (pin "11") (pinfunction "CLR_11") (pintype "input"))
    )
    (net (code "2") (name "/+3.75") (class "Default")
      (node (ref "D31") (pin "C") (pinfunction "C_C") (pintype "passive"))
      (node (ref "D32") (pin "C") (pinfunction "C_C") (pintype "passive"))
      (node (ref "D33") (pin "C") (pinfunction "C_C") (pintype "passive"))
      (node (ref "D34") (pin "C") (pinfunction "C_C") (pintype "passive"))
      (node (ref "D35") (pin "C") (pinfunction "C_C") (pintype "passive"))
      (node (ref "D36") (pin "C") (pinfunction "C_C") (pintype "passive"))
      (node (ref "D37") (pin "C") (pinfunction "C_C") (pintype "passive"))
      (node (ref "D38") (pin "C") (pinfunction "C_C") (pintype "passive"))
      (node (ref "D40") (pin "C") (pinfunction "C_C") (pintype "passive"))
      (node (ref "D41") (pin "C") (pinfunction "C_C") (pintype "passive"))
      (node (ref "D42") (pin "C") (pinfunction "C_C") (pintype "passive"))
      (node (ref "D43") (pin "C") (pinfunction "C_C") (pintype "passive"))
      (node (ref "D53") (pin "A") (pinfunction "A_A") (pintype "passive"))
      (node (ref "R76") (pin "1") (pinfunction "1_1") (pintype "passive"))
    )
    (net (code "3") (name "/AC_TO_DATA") (class "Default")
      (node (ref "E25") (pin "8") (pinfunction "I0_8") (pintype "input"))
      (node (ref "E25") (pin "9") (pinfunction "I1_9") (pintype "input"))
      (node (ref "E29") (pin "13") (pinfunction "O_13") (pintype "output"))
      (node (ref "E29") (pin "4") (pinfunction "O_4") (pintype "output"))
      (node (ref "E31") (pin "11") (pinfunction "I0_11") (pintype "input"))
      (node (ref "E31") (pin "3") (pinfunction "I1_3") (pintype "input"))
      (node (ref "E31") (pin "6") (pinfunction "I1_6") (pintype "input"))
      (node (ref "E31") (pin "8") (pinfunction "I0_8") (pintype "input"))
      (node (ref "E34") (pin "11") (pinfunction "I0_11") (pintype "input"))
      (node (ref "E34") (pin "3") (pinfunction "I1_3") (pintype "input"))
      (node (ref "E34") (pin "6") (pinfunction "I1_6") (pintype "input"))
      (node (ref "E34") (pin "8") (pinfunction "I0_8") (pintype "input"))
      (node (ref "E40") (pin "11") (pinfunction "I0_11") (pintype "input"))
      (node (ref "E40") (pin "3") (pinfunction "I1_3") (pintype "input"))
      (node (ref "E40") (pin "5") (pinfunction "I0_5") (pintype "input"))
      (node (ref "E40") (pin "9") (pinfunction "I1_9") (pintype "input"))
    )
    (net (code "4") (name "/BINIT") (class "Default")
      (node (ref "D42") (pin "A") (pinfunction "A_A") (pintype "passive"))
      (node (ref "E27") (pin "6") (pinfunction "O_6") (pintype "open_collector"))
      (node (ref "J2") (pin "TT") (pinfunction "P$2_TT") (pintype "bidirectional"))
      (node (ref "Q6") (pin "1") (pinfunction "E_1") (pintype "passive"))
    )
    (net (code "5") (name "/BIOP1") (class "Default")
      (node (ref "D32") (pin "A") (pinfunction "A_A") (pintype "passive"))
      (node (ref "E14") (pin "2") (pinfunction "O_2") (pintype "open_collector"))
      (node (ref "J2") (pin "V") (pinfunction "P$2_V") (pintype "bidirectional"))
      (node (ref "Q1") (pin "1") (pinfunction "E_1") (pintype "passive"))
    )
    (net (code "6") (name "/BIOP2") (class "Default")
      (node (ref "D34") (pin "A") (pinfunction "A_A") (pintype "passive"))
      (node (ref "E14") (pin "6") (pinfunction "O_6") (pintype "open_collector"))
      (node (ref "J2") (pin "Z") (pinfunction "P$2_Z") (pintype "bidirectional"))
      (node (ref "Q2") (pin "1") (pinfunction "E_1") (pintype "passive"))
    )
    (net (code "7") (name "/BIOP4") (class "Default")
      (node (ref "D36") (pin "A") (pinfunction "A_A") (pintype "passive"))
      (node (ref "E14") (pin "10") (pinfunction "O_10") (pintype "open_collector"))
      (node (ref "J2") (pin "DD") (pinfunction "P$2_DD") (pintype "bidirectional"))
      (node (ref "Q3") (pin "1") (pinfunction "E_1") (pintype "passive"))
    )
    (net (code "8") (name "/BMB00") (class "Default")
      (node (ref "D13") (pin "A") (pinfunction "A_A") (pintype "passive"))
      (node (ref "E13") (pin "10") (pinfunction "O_10") (pintype "open_collector"))
      (node (ref "J1") (pin "D") (pinfunction "P$2_D") (pintype "bidirectional"))
      (node (ref "R25") (pin "1") (pinfunction "1_1") (pintype "passive"))
    )
    (net (code "9") (name "/BMB01") (class "Default")
      (node (ref "D14") (pin "A") (pinfunction "A_A") (pintype "passive"))
      (node (ref "E13") (pin "8") (pinfunction "O_8") (pintype "open_collector"))
      (node (ref "J1") (pin "J") (pinfunction "P$2_J") (pintype "bidirectional"))
      (node (ref "R26") (pin "1") (pinfunction "1_1") (pintype "passive"))
    )
    (net (code "10") (name "/BMB02") (class "Default")
      (node (ref "D15") (pin "A") (pinfunction "A_A") (pintype "passive"))
      (node (ref "E13") (pin "6") (pinfunction "O_6") (pintype "open_collector"))
      (node (ref "J1") (pin "N") (pinfunction "P$2_N") (pintype "bidirectional"))
      (node (ref "R27") (pin "1") (pinfunction "1_1") (pintype "passive"))
    )
    (net (code "11") (name "/BMB03") (class "Default")
      (node (ref "D17") (pin "A") (pinfunction "A_A") (pintype "passive"))
      (node (ref "E13") (pin "12") (pinfunction "O_12") (pintype "open_collector"))
      (node (ref "E13") (pin "4") (pinfunction "O_4") (pintype "open_collector"))
      (node (ref "J1") (pin "X") (pinfunction "P$2_X") (pintype "bidirectional"))
      (node (ref "R29") (pin "1") (pinfunction "1_1") (pintype "passive"))
    )
    (net (code "12") (name "/BMB04") (class "Default")
      (node (ref "D19") (pin "A") (pinfunction "A_A") (pintype "passive"))
      (node (ref "E18") (pin "6") (pinfunction "O_6") (pintype "open_collector"))
      (node (ref "E18") (pin "8") (pinfunction "O_8") (pintype "open_collector"))
      (node (ref "J1") (pin "FF") (pinfunction "P$2_FF") (pintype "bidirectional"))
      (node (ref "R31") (pin "1") (pinfunction "1_1") (pintype "passive"))
    )
    (net (code "13") (name "/BMB05") (class "Default")
      (node (ref "D21") (pin "A") (pinfunction "A_A") (pintype "passive"))
      (node (ref "E18") (pin "10") (pinfunction "O_10") (pintype "open_collector"))
      (node (ref "E18") (pin "4") (pinfunction "O_4") (pintype "open_collector"))
      (node (ref "J1") (pin "RR") (pinfunction "P$2_RR") (pintype "bidirectional"))
      (node (ref "R33") (pin "1") (pinfunction "1_1") (pintype "passive"))
    )
    (net (code "14") (name "/BMB06") (class "Default")
      (node (ref "D23") (pin "A") (pinfunction "A_A") (pintype "passive"))
      (node (ref "E18") (pin "12") (pinfunction "O_12") (pintype "open_collector"))
      (node (ref "E18") (pin "2") (pinfunction "O_2") (pintype "open_collector"))
      (node (ref "J1") (pin "L") (pinfunction "P$2_L") (pintype "bidirectional"))
      (node (ref "R35") (pin "1") (pinfunction "1_1") (pintype "passive"))
    )
    (net (code "15") (name "/BMB07") (class "Default")
      (node (ref "D25") (pin "A") (pinfunction "A_A") (pintype "passive"))
      (node (ref "E22") (pin "10") (pinfunction "O_10") (pintype "open_collector"))
      (node (ref "E22") (pin "4") (pinfunction "O_4") (pintype "open_collector"))
      (node (ref "J1") (pin "V") (pinfunction "P$2_V") (pintype "bidirectional"))
      (node (ref "R37") (pin "1") (pinfunction "1_1") (pintype "passive"))
    )
    (net (code "16") (name "/BMB08") (class "Default")
      (node (ref "D27") (pin "A") (pinfunction "A_A") (pintype "passive"))
      (node (ref "E22") (pin "6") (pinfunction "O_6") (pintype "open_collector"))
      (node (ref "E22") (pin "8") (pinfunction "O_8") (pintype "open_collector"))
      (node (ref "J1") (pin "DD") (pinfunction "P$2_DD") (pintype "bidirectional"))
      (node (ref "R39") (pin "1") (pinfunction "1_1") (pintype "passive"))
    )
    (net (code "17") (name "/BMB09") (class "Default")
      (node (ref "D28") (pin "A") (pinfunction "A_A") (pintype "passive"))
      (node (ref "E22") (pin "12") (pinfunction "O_12") (pintype "open_collector"))
      (node (ref "J1") (pin "JJ") (pinfunction "P$2_JJ") (pintype "bidirectional"))
      (node (ref "R40") (pin "1") (pinfunction "1_1") (pintype "passive"))
    )
    (net (code "18") (name "/BMB10") (class "Default")
      (node (ref "D29") (pin "A") (pinfunction "A_A") (pintype "passive"))
      (node (ref "E22") (pin "2") (pinfunction "O_2") (pintype "open_collector"))
      (node (ref "J1") (pin "NN") (pinfunction "P$2_NN") (pintype "bidirectional"))
      (node (ref "R42") (pin "1") (pinfunction "1_1") (pintype "passive"))
    )
    (net (code "19") (name "/BMB11") (class "Default")
      (node (ref "D30") (pin "A") (pinfunction "A_A") (pintype "passive"))
      (node (ref "E13") (pin "2") (pinfunction "O_2") (pintype "open_collector"))
      (node (ref "J1") (pin "TT") (pinfunction "P$2_TT") (pintype "bidirectional"))
      (node (ref "R43") (pin "1") (pinfunction "1_1") (pintype "passive"))
    )
    (net (code "20") (name "/BTS1") (class "Default")
      (node (ref "D40") (pin "A") (pinfunction "A_A") (pintype "passive"))
      (node (ref "E27") (pin "2") (pinfunction "O_2") (pintype "open_collector"))
      (node (ref "J2") (pin "NN") (pinfunction "P$2_NN") (pintype "bidirectional"))
      (node (ref "Q5") (pin "1") (pinfunction "E_1") (pintype "passive"))
    )
    (net (code "21") (name "/BTS3") (class "Default")
      (node (ref "D38") (pin "A") (pinfunction "A_A") (pintype "passive"))
      (node (ref "E27") (pin "10") (pinfunction "O_10") (pintype "open_collector"))
      (node (ref "J2") (pin "JJ") (pinfunction "P$2_JJ") (pintype "bidirectional"))
      (node (ref "Q4") (pin "1") (pinfunction "E_1") (pintype "passive"))
    )
    (net (code "22") (name "/INIT") (class "Default")
      (node (ref "E30") (pin "7") (pinfunction "I1_7") (pintype "input"))
      (node (ref "U$2") (pin "CR1") (pinfunction "1_CR1") (pintype "bidirectional"))
    )
    (net (code "23") (name "/IOP") (class "Default")
      (node (ref "E11") (pin "10") (pinfunction "I1_10") (pintype "input"))
      (node (ref "E24") (pin "9") (pinfunction "I0_9") (pintype "input"))
      (node (ref "E25") (pin "11") (pinfunction "I0_11") (pintype "input"))
      (node (ref "E26") (pin "11") (pinfunction "I_11") (pintype "input"))
      (node (ref "E26") (pin "5") (pinfunction "I_5") (pintype "input"))
      (node (ref "E6") (pin "9") (pinfunction "Q_9") (pintype "output"))
      (node (ref "E8") (pin "13") (pinfunction "I2_13") (pintype "input"))
      (node (ref "E8") (pin "3") (pinfunction "I0_3") (pintype "input"))
    )
    (net (code "24") (name "/POWER_OK") (class "Default")
      (node (ref "E6") (pin "10") (pinfunction "PRE_10") (pintype "input"))
      (node (ref "E9") (pin "1") (pinfunction "CLR_1") (pintype "input"))
      (node (ref "U$2") (pin "BV2") (pinfunction "1_BV2") (pintype "bidirectional"))
    )
    (net (code "25") (name "/STROBE") (class "Default")
      (node (ref "E1") (pin "8") (pinfunction "I0_8") (pintype "input"))
      (node (ref "E1") (pin "9") (pinfunction "I1_9") (pintype "input"))
      (node (ref "E25") (pin "2") (pinfunction "I0_2") (pintype "input"))
      (node (ref "E25") (pin "3") (pinfunction "I1_3") (pintype "input"))
      (node (ref "E3") (pin "5") (pinfunction "Q_5") (pintype "output"))
      (node (ref "E9") (pin "11") (pinfunction "CLK_11") (pintype "input"))
    )
    (net (code "26") (name "/TP1") (class "Default")
      (node (ref "E10") (pin "7") (pinfunction "I1_7") (pintype "input"))
      (node (ref "U$2") (pin "CD2") (pinfunction "1_CD2") (pintype "bidirectional"))
    )
    (net (code "27") (name "/TP2") (class "Default")
      (node (ref "E15") (pin "9") (pinfunction "I0_9") (pintype "input"))
      (node (ref "U$2") (pin "CE2") (pinfunction "1_CE2") (pintype "bidirectional"))
    )
    (net (code "28") (name "/TP3") (class "Default")
      (node (ref "E15") (pin "12") (pinfunction "I1_12") (pintype "input"))
      (node (ref "U$2") (pin "CH2") (pinfunction "1_CH2") (pintype "bidirectional"))
    )
    (net (code "29") (name "/TP_DB1") (class "Default")
      (node (ref "E25") (pin "5") (pinfunction "I0_5") (pintype "input"))
      (node (ref "E25") (pin "6") (pinfunction "I1_6") (pintype "input"))
      (node (ref "E26") (pin "8") (pinfunction "O_8") (pintype "output"))
      (node (ref "E28") (pin "2") (pinfunction "I0_2") (pintype "input"))
      (node (ref "E28") (pin "5") (pinfunction "I0_5") (pintype "input"))
      (node (ref "U$2") (pin "DB1") (pinfunction "1_DB1") (pintype "bidirectional"))
    )
    (net (code "30") (name "/~{AC00}") (class "Default")
      (node (ref "E23") (pin "2") (pinfunction "CLAMP_2") (pintype "input"))
      (node (ref "E24") (pin "5") (pinfunction "I3_5") (pintype "input"))
      (node (ref "E38") (pin "9") (pinfunction "I_9") (pintype "input"))
      (node (ref "J3") (pin "D") (pinfunction "P$2_D") (pintype "bidirectional"))
      (node (ref "R1") (pin "1") (pinfunction "1_1") (pintype "passive"))
    )
    (net (code "31") (name "/~{AC01}") (class "Default")
      (node (ref "E23") (pin "3") (pinfunction "CLAMP_3") (pintype "input"))
      (node (ref "E24") (pin "4") (pinfunction "I2_4") (pintype "input"))
      (node (ref "E38") (pin "13") (pinfunction "I_13") (pintype "input"))
      (node (ref "J3") (pin "J") (pinfunction "P$2_J") (pintype "bidirectional"))
      (node (ref "R2") (pin "1") (pinfunction "1_1") (pintype "passive"))
    )
    (net (code "32") (name "/~{AC02}") (class "Default")
      (node (ref "E38") (pin "3") (pinfunction "I_3") (pintype "input"))
      (node (ref "E39") (pin "11") (pinfunction "I6_11") (pintype "input"))
      (node (ref "E42") (pin "2") (pinfunction "CLAMP_2") (pintype "input"))
      (node (ref "J3") (pin "N") (pinfunction "P$2_N") (pintype "bidirectional"))
      (node (ref "R3") (pin "1") (pinfunction "1_1") (pintype "passive"))
    )
    (net (code "33") (name "/~{AC03}") (class "Default")
      (node (ref "E39") (pin "6") (pinfunction "I5_6") (pintype "input"))
      (node (ref "E41") (pin "9") (pinfunction "I_9") (pintype "input"))
      (node (ref "E42") (pin "7") (pinfunction "CLAMP_7") (pintype "input"))
      (node (ref "J3") (pin "T") (pinfunction "P$2_T") (pintype "bidirectional"))
      (node (ref "R4") (pin "1") (pinfunction "1_1") (pintype "passive"))
    )
    (net (code "34") (name "/~{AC04}") (class "Default")
      (node (ref "E39") (pin "1") (pinfunction "I0_1") (pintype "input"))
      (node (ref "E41") (pin "11") (pinfunction "I_11") (pintype "input"))
      (node (ref "E42") (pin "12") (pinfunction "CLAMP_12") (pintype "input"))
      (node (ref "J3") (pin "X") (pinfunction "P$2_X") (pintype "bidirectional"))
      (node (ref "R5") (pin "1") (pinfunction "1_1") (pintype "passive"))
    )
    (net (code "35") (name "/~{AC05}") (class "Default")
      (node (ref "E39") (pin "2") (pinfunction "I1_2") (pintype "input"))
      (node (ref "E41") (pin "13") (pinfunction "I_13") (pintype "input"))
      (node (ref "E42") (pin "11") (pinfunction "CLAMP_11") (pintype "input"))
      (node (ref "J3") (pin "BB") (pinfunction "P$2_BB") (pintype "bidirectional"))
      (node (ref "R6") (pin "1") (pinfunction "1_1") (pintype "passive"))
    )
    (net (code "36") (name "/~{AC06}") (class "Default")
      (node (ref "E39") (pin "3") (pinfunction "I2_3") (pintype "input"))
      (node (ref "E41") (pin "3") (pinfunction "I_3") (pintype "input"))
      (node (ref "E42") (pin "9") (pinfunction "CLAMP_9") (pintype "input"))
      (node (ref "J3") (pin "FF") (pinfunction "P$2_FF") (pintype "bidirectional"))
      (node (ref "R7") (pin "1") (pinfunction "1_1") (pintype "passive"))
    )
    (net (code "37") (name "/~{AC07}") (class "Default")
      (node (ref "E39") (pin "4") (pinfunction "I3_4") (pintype "input"))
      (node (ref "E41") (pin "1") (pinfunction "I_1") (pintype "input"))
      (node (ref "E42") (pin "8") (pinfunction "CLAMP_8") (pintype "input"))
      (node (ref "J3") (pin "LL") (pinfunction "P$2_LL") (pintype "bidirectional"))
      (node (ref "R8") (pin "1") (pinfunction "1_1") (pintype "passive"))
    )
    (net (code "38") (name "/~{AC08}") (class "Default")
      (node (ref "E39") (pin "5") (pinfunction "I4_5") (pintype "input"))
      (node (ref "E41") (pin "5") (pinfunction "I_5") (pintype "input"))
      (node (ref "E42") (pin "5") (pinfunction "CLAMP_5") (pintype "input"))
      (node (ref "J3") (pin "RR") (pinfunction "P$2_RR") (pintype "bidirectional"))
      (node (ref "R9") (pin "1") (pinfunction "1_1") (pintype "passive"))
    )
    (net (code "39") (name "/~{AC09}") (class "Default")
      (node (ref "E23") (pin "5") (pinfunction "CLAMP_5") (pintype "input"))
      (node (ref "E24") (pin "2") (pinfunction "I1_2") (pintype "input"))
      (node (ref "E38") (pin "11") (pinfunction "I_11") (pintype "input"))
      (node (ref "J3") (pin "F") (pinfunction "P$2_F") (pintype "bidirectional"))
      (node (ref "R10") (pin "1") (pinfunction "1_1") (pintype "passive"))
    )
    (net (code "40") (name "/~{AC10}") (class "Default")
      (node (ref "E23") (pin "7") (pinfunction "CLAMP_7") (pintype "input"))
      (node (ref "E24") (pin "1") (pinfunction "I0_1") (pintype "input"))
      (node (ref "E38") (pin "1") (pinfunction "I_1") (pintype "input"))
      (node (ref "J3") (pin "L") (pinfunction "P$2_L") (pintype "bidirectional"))
      (node (ref "R11") (pin "1") (pinfunction "1_1") (pintype "passive"))
    )
    (net (code "41") (name "/~{AC11}") (class "Default")
      (node (ref "E38") (pin "5") (pinfunction "I_5") (pintype "input"))
      (node (ref "E39") (pin "12") (pinfunction "I7_12") (pintype "input"))
      (node (ref "E42") (pin "3") (pinfunction "CLAMP_3") (pintype "input"))
      (node (ref "J3") (pin "R") (pinfunction "P$2_R") (pintype "bidirectional"))
      (node (ref "R12") (pin "1") (pinfunction "1_1") (pintype "passive"))
    )
    (net (code "42") (name "/~{BAC00}") (class "Default")
      (node (ref "D1") (pin "A") (pinfunction "A_A") (pintype "passive"))
      (node (ref "E33") (pin "8") (pinfunction "O_8") (pintype "open_collector"))
      (node (ref "J2") (pin "D") (pinfunction "P$2_D") (pintype "bidirectional"))
      (node (ref "R13") (pin "1") (pinfunction "1_1") (pintype "passive"))
    )
    (net (code "43") (name "/~{BAC01}") (class "Default")
      (node (ref "D2") (pin "A") (pinfunction "A_A") (pintype "passive"))
      (node (ref "E33") (pin "12") (pinfunction "O_12") (pintype "open_collector"))
      (node (ref "J2") (pin "J") (pinfunction "P$2_J") (pintype "bidirectional"))
      (node (ref "R14") (pin "1") (pinfunction "1_1") (pintype "passive"))
    )
    (net (code "44") (name "/~{BAC02}") (class "Default")
      (node (ref "D3") (pin "A") (pinfunction "A_A") (pintype "passive"))
      (node (ref "E33") (pin "4") (pinfunction "O_4") (pintype "open_collector"))
      (node (ref "J2") (pin "N") (pinfunction "P$2_N") (pintype "bidirectional"))
      (node (ref "R15") (pin "1") (pinfunction "1_1") (pintype "passive"))
    )
    (net (code "45") (name "/~{BAC03}") (class "Default")
      (node (ref "D4") (pin "A") (pinfunction "A_A") (pintype "passive"))
      (node (ref "E36") (pin "8") (pinfunction "O_8") (pintype "open_collector"))
      (node (ref "J2") (pin "T") (pinfunction "P$2_T") (pintype "bidirectional"))
      (node (ref "R16") (pin "1") (pinfunction "1_1") (pintype "passive"))
    )
    (net (code "46") (name "/~{BAC04}") (class "Default")
      (node (ref "D5") (pin "A") (pinfunction "A_A") (pintype "passive"))
      (node (ref "E36") (pin "10") (pinfunction "O_10") (pintype "open_collector"))
      (node (ref "J2") (pin "X") (pinfunction "P$2_X") (pintype "bidirectional"))
      (node (ref "R17") (pin "1") (pinfunction "1_1") (pintype "passive"))
    )
    (net (code "47") (name "/~{BAC05}") (class "Default")
      (node (ref "D6") (pin "A") (pinfunction "A_A") (pintype "passive"))
      (node (ref "E36") (pin "12") (pinfunction "O_12") (pintype "open_collector"))
      (node (ref "J2") (pin "BB") (pinfunction "P$2_BB") (pintype "bidirectional"))
      (node (ref "R18") (pin "1") (pinfunction "1_1") (pintype "passive"))
    )
    (net (code "48") (name "/~{BAC06}") (class "Default")
      (node (ref "D7") (pin "A") (pinfunction "A_A") (pintype "passive"))
      (node (ref "E36") (pin "6") (pinfunction "O_6") (pintype "open_collector"))
      (node (ref "J2") (pin "FF") (pinfunction "P$2_FF") (pintype "bidirectional"))
      (node (ref "R19") (pin "1") (pinfunction "1_1") (pintype "passive"))
    )
    (net (code "49") (name "/~{BAC07}") (class "Default")
      (node (ref "D8") (pin "A") (pinfunction "A_A") (pintype "passive"))
      (node (ref "E36") (pin "4") (pinfunction "O_4") (pintype "open_collector"))
      (node (ref "J2") (pin "LL") (pinfunction "P$2_LL") (pintype "bidirectional"))
      (node (ref "R20") (pin "1") (pinfunction "1_1") (pintype "passive"))
    )
    (net (code "50") (name "/~{BAC08}") (class "Default")
      (node (ref "D9") (pin "A") (pinfunction "A_A") (pintype "passive"))
      (node (ref "E36") (pin "2") (pinfunction "O_2") (pintype "open_collector"))
      (node (ref "J2") (pin "RR") (pinfunction "P$2_RR") (pintype "bidirectional"))
      (node (ref "R21") (pin "1") (pinfunction "1_1") (pintype "passive"))
    )
    (net (code "51") (name "/~{BAC09}") (class "Default")
      (node (ref "D10") (pin "A") (pinfunction "A_A") (pintype "passive"))
      (node (ref "E33") (pin "10") (pinfunction "O_10") (pintype "open_collector"))
      (node (ref "J2") (pin "F") (pinfunction "P$2_F") (pintype "bidirectional"))
      (node (ref "R22") (pin "1") (pinfunction "1_1") (pintype "passive"))
    )
    (net (code "52") (name "/~{BAC10}") (class "Default")
      (node (ref "D11") (pin "A") (pinfunction "A_A") (pintype "passive"))
      (node (ref "E33") (pin "2") (pinfunction "O_2") (pintype "open_collector"))
      (node (ref "J2") (pin "L") (pinfunction "P$2_L") (pintype "bidirectional"))
      (node (ref "R23") (pin "1") (pinfunction "1_1") (pintype "passive"))
    )
    (net (code "53") (name "/~{BAC11}") (class "Default")
      (node (ref "D12") (pin "A") (pinfunction "A_A") (pintype "passive"))
      (node (ref "E33") (pin "6") (pinfunction "O_6") (pintype "open_collector"))
      (node (ref "J2") (pin "R") (pinfunction "P$2_R") (pintype "bidirectional"))
      (node (ref "R24") (pin "1") (pinfunction "1_1") (pintype "passive"))
    )
    (net (code "54") (name "/~{BMB03}") (class "Default")
      (node (ref "D16") (pin "A") (pinfunction "A_A") (pintype "passive"))
      (node (ref "E17") (pin "12") (pinfunction "O_12") (pintype "open_collector"))
      (node (ref "E17") (pin "2") (pinfunction "O_2") (pintype "open_collector"))
      (node (ref "J1") (pin "T") (pinfunction "P$2_T") (pintype "bidirectional"))
      (node (ref "R28") (pin "1") (pinfunction "1_1") (pintype "passive"))
    )
    (net (code "55") (name "/~{BMB04}") (class "Default")
      (node (ref "D18") (pin "A") (pinfunction "A_A") (pintype "passive"))
      (node (ref "E17") (pin "10") (pinfunction "O_10") (pintype "open_collector"))
      (node (ref "E17") (pin "4") (pinfunction "O_4") (pintype "open_collector"))
      (node (ref "J1") (pin "BB") (pinfunction "P$2_BB") (pintype "bidirectional"))
      (node (ref "R30") (pin "1") (pinfunction "1_1") (pintype "passive"))
    )
    (net (code "56") (name "/~{BMB05}") (class "Default")
      (node (ref "D20") (pin "A") (pinfunction "A_A") (pintype "passive"))
      (node (ref "E17") (pin "6") (pinfunction "O_6") (pintype "open_collector"))
      (node (ref "E17") (pin "8") (pinfunction "O_8") (pintype "open_collector"))
      (node (ref "J1") (pin "LL") (pinfunction "P$2_LL") (pintype "bidirectional"))
      (node (ref "R32") (pin "1") (pinfunction "1_1") (pintype "passive"))
    )
    (net (code "57") (name "/~{BMB06}") (class "Default")
      (node (ref "D22") (pin "A") (pinfunction "A_A") (pintype "passive"))
      (node (ref "E21") (pin "6") (pinfunction "O_6") (pintype "open_collector"))
      (node (ref "E21") (pin "8") (pinfunction "O_8") (pintype "open_collector"))
      (node (ref "J1") (pin "F") (pinfunction "P$2_F") (pintype "bidirectional"))
      (node (ref "R34") (pin "1") (pinfunction "1_1") (pintype "passive"))
    )
    (net (code "58") (name "/~{BMB07}") (class "Default")
      (node (ref "D24") (pin "A") (pinfunction "A_A") (pintype "passive"))
      (node (ref "E21") (pin "10") (pinfunction "O_10") (pintype "open_collector"))
      (node (ref "E21") (pin "4") (pinfunction "O_4") (pintype "open_collector"))
      (node (ref "J1") (pin "R") (pinfunction "P$2_R") (pintype "bidirectional"))
      (node (ref "R36") (pin "1") (pinfunction "1_1") (pintype "passive"))
    )
    (net (code "59") (name "/~{BMB08}") (class "Default")
      (node (ref "D26") (pin "A") (pinfunction "A_A") (pintype "passive"))
      (node (ref "E21") (pin "12") (pinfunction "O_12") (pintype "open_collector"))
      (node (ref "E21") (pin "2") (pinfunction "O_2") (pintype "open_collector"))
      (node (ref "J1") (pin "Z") (pinfunction "P$2_Z") (pintype "bidirectional"))
      (node (ref "R38") (pin "1") (pinfunction "1_1") (pintype "passive"))
    )
    (net (code "60") (name "/~{BRUN}") (class "Default")
      (node (ref "D39") (pin "A") (pinfunction "A_A") (pintype "passive"))
      (node (ref "J3") (pin "JJ") (pinfunction "P$2_JJ") (pintype "bidirectional"))
      (node (ref "Q7") (pin "3") (pinfunction "C_3") (pintype "passive"))
      (node (ref "R41") (pin "1") (pinfunction "1_1") (pintype "passive"))
    )
    (net (code "61") (name "/~{C0}") (class "Default")
      (node (ref "E25") (pin "13") (pinfunction "O_13") (pintype "open_collector"))
      (node (ref "U$2") (pin "CE1") (pinfunction "1_CE1") (pintype "bidirectional"))
    )
    (net (code "62") (name "/~{C1}") (class "Default")
      (node (ref "E25") (pin "10") (pinfunction "O_10") (pintype "open_collector"))
      (node (ref "U$2") (pin "CH1") (pinfunction "1_CH1") (pintype "bidirectional"))
    )
    (net (code "63") (name "/~{C2}") (class "Default")
      (node (ref "E25") (pin "4") (pinfunction "O_4") (pintype "open_collector"))
      (node (ref "U$2") (pin "CJ1") (pinfunction "1_CJ1") (pintype "bidirectional"))
    )
    (net (code "64") (name "/~{CEN}") (class "Default")
      (node (ref "E26") (pin "9") (pinfunction "I_9") (pintype "input"))
      (node (ref "E9") (pin "6") (pinfunction "~{Q}_6") (pintype "output"))
    )
    (net (code "65") (name "/~{CLEARB}") (class "Default")
      (node (ref "E23") (pin "9") (pinfunction "CLAMP_9") (pintype "input"))
      (node (ref "E26") (pin "13") (pinfunction "I_13") (pintype "input"))
      (node (ref "J3") (pin "DD") (pinfunction "P$2_DD") (pintype "bidirectional"))
      (node (ref "R64") (pin "1") (pinfunction "1_1") (pintype "passive"))
    )
    (net (code "66") (name "/~{DATA0}") (class "Default")
      (node (ref "E31") (pin "13") (pinfunction "O_13") (pintype "open_collector"))
      (node (ref "E32") (pin "9") (pinfunction "I0_9") (pintype "input"))
      (node (ref "U$2") (pin "AR1") (pinfunction "1_AR1") (pintype "bidirectional"))
    )
    (net (code "67") (name "/~{DATA1}") (class "Default")
      (node (ref "E31") (pin "10") (pinfunction "O_10") (pintype "open_collector"))
      (node (ref "E32") (pin "12") (pinfunction "I1_12") (pintype "input"))
      (node (ref "U$2") (pin "AS1") (pinfunction "1_AS1") (pintype "bidirectional"))
    )
    (net (code "68") (name "/~{DATA2}") (class "Default")
      (node (ref "E31") (pin "1") (pinfunction "O_1") (pintype "open_collector"))
      (node (ref "E32") (pin "7") (pinfunction "I1_7") (pintype "input"))
      (node (ref "U$2") (pin "AU1") (pinfunction "1_AU1") (pintype "bidirectional"))
    )
    (net (code "69") (name "/~{DATA3}") (class "Default")
      (node (ref "E31") (pin "4") (pinfunction "O_4") (pintype "open_collector"))
      (node (ref "E32") (pin "4") (pinfunction "I0_4") (pintype "input"))
      (node (ref "U$2") (pin "AV1") (pinfunction "1_AV1") (pintype "bidirectional"))
    )
    (net (code "70") (name "/~{DATA4}") (class "Default")
      (node (ref "E34") (pin "13") (pinfunction "O_13") (pintype "open_collector"))
      (node (ref "E35") (pin "9") (pinfunction "I0_9") (pintype "input"))
      (node (ref "U$2") (pin "BR1") (pinfunction "1_BR1") (pintype "bidirectional"))
    )
    (net (code "71") (name "/~{DATA5}") (class "Default")
      (node (ref "E34") (pin "10") (pinfunction "O_10") (pintype "open_collector"))
      (node (ref "E35") (pin "11") (pinfunction "I0_11") (pintype "input"))
      (node (ref "U$2") (pin "BS1") (pinfunction "1_BS1") (pintype "bidirectional"))
    )
    (net (code "72") (name "/~{DATA6}") (class "Default")
      (node (ref "E34") (pin "1") (pinfunction "O_1") (pintype "open_collector"))
      (node (ref "E35") (pin "7") (pinfunction "I1_7") (pintype "input"))
      (node (ref "U$2") (pin "BU1") (pinfunction "1_BU1") (pintype "bidirectional"))
    )
    (net (code "73") (name "/~{DATA7}") (class "Default")
      (node (ref "E34") (pin "4") (pinfunction "O_4") (pintype "open_collector"))
      (node (ref "E35") (pin "4") (pinfunction "I0_4") (pintype "input"))
      (node (ref "U$2") (pin "BV1") (pinfunction "1_BV1") (pintype "bidirectional"))
    )
    (net (code "74") (name "/~{DATA8}") (class "Default")
      (node (ref "E37") (pin "4") (pinfunction "I0_4") (pintype "input"))
      (node (ref "E40") (pin "13") (pinfunction "O_13") (pintype "open_collector"))
      (node (ref "U$2") (pin "DR1") (pinfunction "1_DR1") (pintype "bidirectional"))
    )
    (net (code "75") (name "/~{DATA9}") (class "Default")
      (node (ref "E37") (pin "7") (pinfunction "I1_7") (pintype "input"))
      (node (ref "E40") (pin "10") (pinfunction "O_10") (pintype "open_collector"))
      (node (ref "U$2") (pin "DS1") (pinfunction "1_DS1") (pintype "bidirectional"))
    )
    (net (code "76") (name "/~{DATA10}") (class "Default")
      (node (ref "E28") (pin "4") (pinfunction "O_4") (pintype "open_collector"))
      (node (ref "E37") (pin "9") (pinfunction "I0_9") (pintype "input"))
      (node (ref "E40") (pin "4") (pinfunction "O_4") (pintype "open_collector"))
      (node (ref "U$2") (pin "DU1") (pinfunction "1_DU1") (pintype "bidirectional"))
    )
    (net (code "77") (name "/~{DATA11}") (class "Default")
      (node (ref "E28") (pin "1") (pinfunction "O_1") (pintype "open_collector"))
      (node (ref "E37") (pin "11") (pinfunction "I0_11") (pintype "input"))
      (node (ref "E40") (pin "1") (pinfunction "O_1") (pintype "open_collector"))
      (node (ref "U$2") (pin "DV1") (pinfunction "1_DV1") (pintype "bidirectional"))
    )
    (net (code "78") (name "/~{DATA_IN}") (class "Default")
      (node (ref "E29") (pin "1") (pinfunction "O_1") (pintype "output"))
      (node (ref "E29") (pin "12") (pinfunction "I1_12") (pintype "input"))
      (node (ref "E29") (pin "5") (pinfunction "I0_5") (pintype "input"))
    )
    (net (code "79") (name "/~{INTERNAL_IO}") (class "Default")
      (node (ref "E28") (pin "11") (pinfunction "I0_11") (pintype "input"))
      (node (ref "E5") (pin "3") (pinfunction "I0_3") (pintype "input"))
      (node (ref "U$2") (pin "CL1") (pinfunction "1_CL1") (pintype "bidirectional"))
    )
    (net (code "80") (name "/~{IOP}") (class "Default")
      (node (ref "E4") (pin "2") (pinfunction "B_2") (pintype "input"))
      (node (ref "E6") (pin "8") (pinfunction "~{Q}_8") (pintype "output"))
    )
    (net (code "81") (name "/~{IRQB}") (class "Default")
      (node (ref "E23") (pin "11") (pinfunction "CLAMP_11") (pintype "input"))
      (node (ref "E26") (pin "3") (pinfunction "I_3") (pintype "input"))
      (node (ref "J3") (pin "Z") (pinfunction "P$2_Z") (pintype "bidirectional"))
      (node (ref "R63") (pin "1") (pinfunction "1_1") (pintype "passive"))
    )
    (net (code "82") (name "/~{IRQ}") (class "Default")
      (node (ref "E28") (pin "10") (pinfunction "O_10") (pintype "open_collector"))
      (node (ref "U$2") (pin "CP1") (pinfunction "1_CP1") (pintype "bidirectional"))
    )
    (net (code "83") (name "/~{MD00}") (class "Default")
      (node (ref "E12") (pin "12") (pinfunction "I1_12") (pintype "input"))
      (node (ref "U$2") (pin "AK1") (pinfunction "1_AK1") (pintype "bidirectional"))
    )
    (net (code "84") (name "/~{MD01}") (class "Default")
      (node (ref "E12") (pin "9") (pinfunction "I0_9") (pintype "input"))
      (node (ref "U$2") (pin "AL1") (pinfunction "1_AL1") (pintype "bidirectional"))
    )
    (net (code "85") (name "/~{MD02}") (class "Default")
      (node (ref "E12") (pin "7") (pinfunction "I1_7") (pintype "input"))
      (node (ref "U$2") (pin "AM1") (pinfunction "1_AM1") (pintype "bidirectional"))
    )
    (net (code "86") (name "/~{MD03}") (class "Default")
      (node (ref "E12") (pin "5") (pinfunction "I1_5") (pintype "input"))
      (node (ref "U$2") (pin "AP1") (pinfunction "1_AP1") (pintype "bidirectional"))
    )
    (net (code "87") (name "/~{MD04}") (class "Default")
      (node (ref "E16") (pin "12") (pinfunction "I1_12") (pintype "input"))
      (node (ref "U$2") (pin "BK1") (pinfunction "1_BK1") (pintype "bidirectional"))
    )
    (net (code "88") (name "/~{MD05}") (class "Default")
      (node (ref "E16") (pin "9") (pinfunction "I0_9") (pintype "input"))
      (node (ref "U$2") (pin "BL1") (pinfunction "1_BL1") (pintype "bidirectional"))
    )
    (net (code "89") (name "/~{MD06}") (class "Default")
      (node (ref "E16") (pin "7") (pinfunction "I1_7") (pintype "input"))
      (node (ref "U$2") (pin "BM1") (pinfunction "1_BM1") (pintype "bidirectional"))
    )
    (net (code "90") (name "/~{MD07}") (class "Default")
      (node (ref "E16") (pin "4") (pinfunction "I0_4") (pintype "input"))
      (node (ref "U$2") (pin "BP1") (pinfunction "1_BP1") (pintype "bidirectional"))
    )
    (net (code "91") (name "/~{MD08}") (class "Default")
      (node (ref "E20") (pin "9") (pinfunction "I0_9") (pintype "input"))
      (node (ref "U$2") (pin "DK1") (pinfunction "1_DK1") (pintype "bidirectional"))
    )
    (net (code "92") (name "/~{MD09}") (class "Default")
      (node (ref "E20") (pin "12") (pinfunction "I1_12") (pintype "input"))
      (node (ref "U$2") (pin "DL1") (pinfunction "1_DL1") (pintype "bidirectional"))
    )
    (net (code "93") (name "/~{MD10}") (class "Default")
      (node (ref "E20") (pin "7") (pinfunction "I1_7") (pintype "input"))
      (node (ref "U$2") (pin "DM1") (pinfunction "1_DM1") (pintype "bidirectional"))
    )
    (net (code "94") (name "/~{MD11}") (class "Default")
      (node (ref "E20") (pin "4") (pinfunction "I0_4") (pintype "input"))
      (node (ref "U$2") (pin "DP1") (pinfunction "1_DP1") (pintype "bidirectional"))
    )
    (net (code "95") (name "/~{N_L_XFR}") (class "Default")
      (node (ref "E28") (pin "13") (pinfunction "O_13") (pintype "open_collector"))
      (node (ref "U$2") (pin "CM1") (pinfunction "1_CM1") (pintype "bidirectional"))
    )
    (net (code "96") (name "/~{PAUSE}") (class "Default")
      (node (ref "E10") (pin "11") (pinfunction "I0_11") (pintype "input"))
      (node (ref "U$2") (pin "CD1") (pinfunction "1_CD1") (pintype "bidirectional"))
    )
    (net (code "97") (name "/~{RUN}") (class "Default")
      (node (ref "E10") (pin "4") (pinfunction "I0_4") (pintype "input"))
      (node (ref "U$2") (pin "BU2") (pinfunction "1_BU2") (pintype "bidirectional"))
    )
    (net (code "98") (name "/~{SKIPB}") (class "Default")
      (node (ref "E23") (pin "12") (pinfunction "CLAMP_12") (pintype "input"))
      (node (ref "E9") (pin "12") (pinfunction "D_12") (pintype "input"))
      (node (ref "J3") (pin "V") (pinfunction "P$2_V") (pintype "bidirectional"))
      (node (ref "R62") (pin "1") (pinfunction "1_1") (pintype "passive"))
    )
    (net (code "99") (name "/~{STOP}") (class "Default")
      (node (ref "E1") (pin "5") (pinfunction "I0_5") (pintype "input"))
      (node (ref "E1") (pin "6") (pinfunction "I1_6") (pintype "input"))
      (node (ref "E8") (pin "12") (pinfunction "O_12") (pintype "output"))
    )
    (net (code "100") (name "/~{STROBE}") (class "Default")
      (node (ref "E1") (pin "10") (pinfunction "O_10") (pintype "open_collector"))
      (node (ref "E25") (pin "1") (pinfunction "O_1") (pintype "open_collector"))
      (node (ref "U$2") (pin "CK1") (pinfunction "1_CK1") (pintype "bidirectional"))
    )
    (net (code "101") (name "/~{TS1}") (class "Default")
      (node (ref "E30") (pin "9") (pinfunction "I0_9") (pintype "input"))
      (node (ref "U$2") (pin "CK2") (pinfunction "1_CK2") (pintype "bidirectional"))
    )
    (net (code "102") (name "/~{TS3}") (class "Default")
      (node (ref "E30") (pin "12") (pinfunction "I1_12") (pintype "input"))
      (node (ref "U$2") (pin "CM2") (pinfunction "1_CM2") (pintype "bidirectional"))
    )
    (net (code "103") (name "GND") (class "Default")
      (node (ref "C1") (pin "2") (pinfunction "2_2") (pintype "passive"))
      (node (ref "C10") (pin "2") (pinfunction "2_2") (pintype "passive"))
      (node (ref "C11") (pin "2") (pinfunction "2_2") (pintype "passive"))
      (node (ref "C12") (pin "2") (pinfunction "2_2") (pintype "passive"))
      (node (ref "C13") (pin "2") (pinfunction "2_2") (pintype "passive"))
      (node (ref "C14") (pin "2") (pinfunction "2_2") (pintype "passive"))
      (node (ref "C15") (pin "2") (pinfunction "2_2") (pintype "passive"))
      (node (ref "C16") (pin "2") (pinfunction "2_2") (pintype "passive"))
      (node (ref "C17") (pin "2") (pinfunction "2_2") (pintype "passive"))
      (node (ref "C18") (pin "2") (pinfunction "2_2") (pintype "passive"))
      (node (ref "C19") (pin "2") (pinfunction "2_2") (pintype "passive"))
      (node (ref "C2") (pin "2") (pinfunction "2_2") (pintype "passive"))
      (node (ref "C20") (pin "-") (pinfunction "-_-") (pintype "passive"))
      (node (ref "C21") (pin "-") (pinfunction "-_-") (pintype "passive"))
      (node (ref "C22") (pin "-") (pinfunction "-_-") (pintype "passive"))
      (node (ref "C23") (pin "2") (pinfunction "2_2") (pintype "passive"))
      (node (ref "C24") (pin "2") (pinfunction "2_2") (pintype "passive"))
      (node (ref "C25") (pin "2") (pinfunction "2_2") (pintype "passive"))
      (node (ref "C3") (pin "2") (pinfunction "2_2") (pintype "passive"))
      (node (ref "C32") (pin "2") (pinfunction "2_2") (pintype "passive"))
      (node (ref "C4") (pin "2") (pinfunction "2_2") (pintype "passive"))
      (node (ref "C5") (pin "2") (pinfunction "2_2") (pintype "passive"))
      (node (ref "C6") (pin "2") (pinfunction "2_2") (pintype "passive"))
      (node (ref "C7") (pin "2") (pinfunction "2_2") (pintype "passive"))
      (node (ref "C8") (pin "2") (pinfunction "2_2") (pintype "passive"))
      (node (ref "C9") (pin "2") (pinfunction "2_2") (pintype "passive"))
      (node (ref "D47") (pin "C") (pinfunction "C_C") (pintype "passive"))
      (node (ref "D52") (pin "C") (pinfunction "C_C") (pintype "passive"))
      (node (ref "E10") (pin "5") (pinfunction "I1_5") (pintype "input"))
      (node (ref "E10") (pin "6") (pinfunction "I0_6") (pintype "input"))
      (node (ref "E12") (pin "10") (pinfunction "I1_10") (pintype "input"))
      (node (ref "E12") (pin "11") (pinfunction "I0_11") (pintype "input"))
      (node (ref "E12") (pin "4") (pinfunction "I0_4") (pintype "input"))
      (node (ref "E12") (pin "6") (pinfunction "I0_6") (pintype "input"))
      (node (ref "E15") (pin "10") (pinfunction "I1_10") (pintype "input"))
      (node (ref "E15") (pin "11") (pinfunction "I0_11") (pintype "input"))
      (node (ref "E16") (pin "10") (pinfunction "I1_10") (pintype "input"))
      (node (ref "E16") (pin "11") (pinfunction "I0_11") (pintype "input"))
      (node (ref "E16") (pin "5") (pinfunction "I1_5") (pintype "input"))
      (node (ref "E16") (pin "6") (pinfunction "I0_6") (pintype "input"))
      (node (ref "E2") (pin "1") (pinfunction "A_1") (pintype "input"))
      (node (ref "E2") (pin "9") (pinfunction "A_9") (pintype "input"))
      (node (ref "E20") (pin "10") (pinfunction "I1_10") (pintype "input"))
      (node (ref "E20") (pin "11") (pinfunction "I0_11") (pintype "input"))
      (node (ref "E20") (pin "5") (pinfunction "I1_5") (pintype "input"))
      (node (ref "E20") (pin "6") (pinfunction "I0_6") (pintype "input"))
      (node (ref "E3") (pin "1") (pinfunction "A_1") (pintype "input"))
      (node (ref "E3") (pin "9") (pinfunction "A_9") (pintype "input"))
      (node (ref "E30") (pin "10") (pinfunction "I1_10") (pintype "input"))
      (node (ref "E30") (pin "11") (pinfunction "I0_11") (pintype "input"))
      (node (ref "E30") (pin "6") (pinfunction "I0_6") (pintype "input"))
      (node (ref "E32") (pin "10") (pinfunction "I1_10") (pintype "input"))
      (node (ref "E32") (pin "11") (pinfunction "I0_11") (pintype "input"))
      (node (ref "E32") (pin "5") (pinfunction "I1_5") (pintype "input"))
      (node (ref "E32") (pin "6") (pinfunction "I0_6") (pintype "input"))
      (node (ref "E35") (pin "10") (pinfunction "I1_10") (pintype "input"))
      (node (ref "E35") (pin "12") (pinfunction "I1_12") (pintype "input"))
      (node (ref "E35") (pin "5") (pinfunction "I1_5") (pintype "input"))
      (node (ref "E35") (pin "6") (pinfunction "I0_6") (pintype "input"))
      (node (ref "E37") (pin "10") (pinfunction "I1_10") (pintype "input"))
      (node (ref "E37") (pin "12") (pinfunction "I1_12") (pintype "input"))
      (node (ref "E37") (pin "5") (pinfunction "I1_5") (pintype "input"))
      (node (ref "E37") (pin "6") (pinfunction "I0_6") (pintype "input"))
      (node (ref "E4") (pin "1") (pinfunction "A_1") (pintype "input"))
      (node (ref "E6") (pin "12") (pinfunction "D_12") (pintype "input"))
      (node (ref "E6") (pin "2") (pinfunction "D_2") (pintype "input"))
      (node (ref "E7") (pin "12") (pinfunction "D_12") (pintype "input"))
      (node (ref "E7") (pin "2") (pinfunction "D_2") (pintype "input"))
      (node (ref "E9") (pin "2") (pinfunction "D_2") (pintype "input"))
      (node (ref "J1") (pin "A") (pinfunction "P$2_A") (pintype "bidirectional"))
      (node (ref "J1") (pin "AA") (pinfunction "P$2_AA") (pintype "bidirectional"))
      (node (ref "J1") (pin "B") (pinfunction "P$2_B") (pintype "bidirectional"))
      (node (ref "J1") (pin "C") (pinfunction "P$2_C") (pintype "bidirectional"))
      (node (ref "J1") (pin "CC") (pinfunction "P$2_CC") (pintype "bidirectional"))
      (node (ref "J1") (pin "E") (pinfunction "P$2_E") (pintype "bidirectional"))
      (node (ref "J1") (pin "EE") (pinfunction "P$2_EE") (pintype "bidirectional"))
      (node (ref "J1") (pin "H") (pinfunction "P$2_H") (pintype "bidirectional"))
      (node (ref "J1") (pin "HH") (pinfunction "P$2_HH") (pintype "bidirectional"))
      (node (ref "J1") (pin "K") (pinfunction "P$2_K") (pintype "bidirectional"))
      (node (ref "J1") (pin "KK") (pinfunction "P$2_KK") (pintype "bidirectional"))
      (node (ref "J1") (pin "M") (pinfunction "P$2_M") (pintype "bidirectional"))
      (node (ref "J1") (pin "MM") (pinfunction "P$2_MM") (pintype "bidirectional"))
      (node (ref "J1") (pin "P") (pinfunction "P$2_P") (pintype "bidirectional"))
      (node (ref "J1") (pin "PP") (pinfunction "P$2_PP") (pintype "bidirectional"))
      (node (ref "J1") (pin "S") (pinfunction "P$2_S") (pintype "bidirectional"))
      (node (ref "J1") (pin "SS") (pinfunction "P$2_SS") (pintype "bidirectional"))
      (node (ref "J1") (pin "U") (pinfunction "P$2_U") (pintype "bidirectional"))
      (node (ref "J1") (pin "UU") (pinfunction "P$2_UU") (pintype "bidirectional"))
      (node (ref "J1") (pin "VV") (pinfunction "P$2_VV") (pintype "bidirectional"))
      (node (ref "J1") (pin "W") (pinfunction "P$2_W") (pintype "bidirectional"))
      (node (ref "J1") (pin "Y") (pinfunction "P$2_Y") (pintype "bidirectional"))
      (node (ref "J2") (pin "A") (pinfunction "P$2_A") (pintype "bidirectional"))
      (node (ref "J2") (pin "AA") (pinfunction "P$2_AA") (pintype "bidirectional"))
      (node (ref "J2") (pin "B") (pinfunction "P$2_B") (pintype "bidirectional"))
      (node (ref "J2") (pin "C") (pinfunction "P$2_C") (pintype "bidirectional"))
      (node (ref "J2") (pin "CC") (pinfunction "P$2_CC") (pintype "bidirectional"))
      (node (ref "J2") (pin "E") (pinfunction "P$2_E") (pintype "bidirectional"))
      (node (ref "J2") (pin "EE") (pinfunction "P$2_EE") (pintype "bidirectional"))
      (node (ref "J2") (pin "H") (pinfunction "P$2_H") (pintype "bidirectional"))
      (node (ref "J2") (pin "HH") (pinfunction "P$2_HH") (pintype "bidirectional"))
      (node (ref "J2") (pin "K") (pinfunction "P$2_K") (pintype "bidirectional"))
      (node (ref "J2") (pin "KK") (pinfunction "P$2_KK") (pintype "bidirectional"))
      (node (ref "J2") (pin "M") (pinfunction "P$2_M") (pintype "bidirectional"))
      (node (ref "J2") (pin "MM") (pinfunction "P$2_MM") (pintype "bidirectional"))
      (node (ref "J2") (pin "P") (pinfunction "P$2_P") (pintype "bidirectional"))
      (node (ref "J2") (pin "PP") (pinfunction "P$2_PP") (pintype "bidirectional"))
      (node (ref "J2") (pin "S") (pinfunction "P$2_S") (pintype "bidirectional"))
      (node (ref "J2") (pin "SS") (pinfunction "P$2_SS") (pintype "bidirectional"))
      (node (ref "J2") (pin "U") (pinfunction "P$2_U") (pintype "bidirectional"))
      (node (ref "J2") (pin "UU") (pinfunction "P$2_UU") (pintype "bidirectional"))
      (node (ref "J2") (pin "VV") (pinfunction "P$2_VV") (pintype "bidirectional"))
      (node (ref "J2") (pin "W") (pinfunction "P$2_W") (pintype "bidirectional"))
      (node (ref "J2") (pin "Y") (pinfunction "P$2_Y") (pintype "bidirectional"))
      (node (ref "J3") (pin "A") (pinfunction "P$2_A") (pintype "bidirectional"))
      (node (ref "J3") (pin "AA") (pinfunction "P$2_AA") (pintype "bidirectional"))
      (node (ref "J3") (pin "B") (pinfunction "P$2_B") (pintype "bidirectional"))
      (node (ref "J3") (pin "C") (pinfunction "P$2_C") (pintype "bidirectional"))
      (node (ref "J3") (pin "CC") (pinfunction "P$2_CC") (pintype "bidirectional"))
      (node (ref "J3") (pin "E") (pinfunction "P$2_E") (pintype "bidirectional"))
      (node (ref "J3") (pin "EE") (pinfunction "P$2_EE") (pintype "bidirectional"))
      (node (ref "J3") (pin "H") (pinfunction "P$2_H") (pintype "bidirectional"))
      (node (ref "J3") (pin "HH") (pinfunction "P$2_HH") (pintype "bidirectional"))
      (node (ref "J3") (pin "K") (pinfunction "P$2_K") (pintype "bidirectional"))
      (node (ref "J3") (pin "KK") (pinfunction "P$2_KK") (pintype "bidirectional"))
      (node (ref "J3") (pin "M") (pinfunction "P$2_M") (pintype "bidirectional"))
      (node (ref "J3") (pin "MM") (pinfunction "P$2_MM") (pintype "bidirectional"))
      (node (ref "J3") (pin "P") (pinfunction "P$2_P") (pintype "bidirectional"))
      (node (ref "J3") (pin "PP") (pinfunction "P$2_PP") (pintype "bidirectional"))
      (node (ref "J3") (pin "S") (pinfunction "P$2_S") (pintype "bidirectional"))
      (node (ref "J3") (pin "SS") (pinfunction "P$2_SS") (pintype "bidirectional"))
      (node (ref "J3") (pin "U") (pinfunction "P$2_U") (pintype "bidirectional"))
      (node (ref "J3") (pin "UU") (pinfunction "P$2_UU") (pintype "bidirectional"))
      (node (ref "J3") (pin "VV") (pinfunction "P$2_VV") (pintype "bidirectional"))
      (node (ref "J3") (pin "W") (pinfunction "P$2_W") (pintype "bidirectional"))
      (node (ref "J3") (pin "Y") (pinfunction "P$2_Y") (pintype "bidirectional"))
      (node (ref "Q7") (pin "1") (pinfunction "E_1") (pintype "passive"))
      (node (ref "R74") (pin "1") (pinfunction "1_1") (pintype "passive"))
      (node (ref "U$2") (pin "AC2") (pinfunction "1_AC2") (pintype "bidirectional"))
      (node (ref "U$2") (pin "AF1") (pinfunction "1_AF1") (pintype "bidirectional"))
      (node (ref "U$2") (pin "AF2") (pinfunction "1_AF2") (pintype "bidirectional"))
      (node (ref "U$2") (pin "AN1") (pinfunction "1_AN1") (pintype "bidirectional"))
      (node (ref "U$2") (pin "AN2") (pinfunction "1_AN2") (pintype "bidirectional"))
      (node (ref "U$2") (pin "AT1") (pinfunction "1_AT1") (pintype "bidirectional"))
      (node (ref "U$2") (pin "AT2") (pinfunction "1_AT2") (pintype "bidirectional"))
      (node (ref "U$2") (pin "BC1") (pinfunction "1_BC1") (pintype "bidirectional"))
      (node (ref "U$2") (pin "BC2") (pinfunction "1_BC2") (pintype "bidirectional"))
      (node (ref "U$2") (pin "BF1") (pinfunction "1_BF1") (pintype "bidirectional"))
      (node (ref "U$2") (pin "BF2") (pinfunction "1_BF2") (pintype "bidirectional"))
      (node (ref "U$2") (pin "BN1") (pinfunction "1_BN1") (pintype "bidirectional"))
      (node (ref "U$2") (pin "BN2") (pinfunction "1_BN2") (pintype "bidirectional"))
      (node (ref "U$2") (pin "BT1") (pinfunction "1_BT1") (pintype "bidirectional"))
      (node (ref "U$2") (pin "BT2") (pinfunction "1_BT2") (pintype "bidirectional"))
      (node (ref "U$2") (pin "CC1") (pinfunction "1_CC1") (pintype "bidirectional"))
      (node (ref "U$2") (pin "CC2") (pinfunction "1_CC2") (pintype "bidirectional"))
      (node (ref "U$2") (pin "CF1") (pinfunction "1_CF1") (pintype "bidirectional"))
      (node (ref "U$2") (pin "CN1") (pinfunction "1_CN1") (pintype "bidirectional"))
      (node (ref "U$2") (pin "CN2") (pinfunction "1_CN2") (pintype "bidirectional"))
      (node (ref "U$2") (pin "CT1") (pinfunction "1_CT1") (pintype "bidirectional"))
      (node (ref "U$2") (pin "CT2") (pinfunction "1_CT2") (pintype "bidirectional"))
      (node (ref "U$2") (pin "DC1") (pinfunction "1_DC1") (pintype "bidirectional"))
      (node (ref "U$2") (pin "DC2") (pinfunction "1_DC2") (pintype "bidirectional"))
      (node (ref "U$2") (pin "DF1") (pinfunction "1_DF1") (pintype "bidirectional"))
      (node (ref "U$2") (pin "DF2") (pinfunction "1_DF2") (pintype "bidirectional"))
      (node (ref "U$2") (pin "DN1") (pinfunction "1_DN1") (pintype "bidirectional"))
      (node (ref "U$2") (pin "DN2") (pinfunction "1_DN2") (pintype "bidirectional"))
      (node (ref "U$2") (pin "DT1") (pinfunction "1_DT1") (pintype "bidirectional"))
      (node (ref "U$2") (pin "DT2") (pinfunction "1_DT2") (pintype "bidirectional"))
    )
    (net (code "104") (name "Net-(D44-PadC)") (class "Default")
      (node (ref "D44") (pin "C") (pinfunction "C_C") (pintype "passive"))
      (node (ref "D45") (pin "A") (pinfunction "A_A") (pintype "passive"))
    )
    (net (code "105") (name "Net-(D45-PadC)") (class "Default")
      (node (ref "D45") (pin "C") (pinfunction "C_C") (pintype "passive"))
      (node (ref "D46") (pin "A") (pinfunction "A_A") (pintype "passive"))
    )
    (net (code "106") (name "Net-(D46-PadC)") (class "Default")
      (node (ref "D46") (pin "C") (pinfunction "C_C") (pintype "passive"))
      (node (ref "D47") (pin "A") (pinfunction "A_A") (pintype "passive"))
    )
    (net (code "107") (name "Net-(D48-PadA)") (class "Default")
      (node (ref "D48") (pin "A") (pinfunction "A_A") (pintype "passive"))
      (node (ref "R77") (pin "1") (pinfunction "1_1") (pintype "passive"))
    )
    (net (code "108") (name "Net-(D48-PadC)") (class "Default")
      (node (ref "D48") (pin "C") (pinfunction "C_C") (pintype "passive"))
      (node (ref "D49") (pin "A") (pinfunction "A_A") (pintype "passive"))
    )
    (net (code "109") (name "Net-(D49-PadC)") (class "Default")
      (node (ref "D49") (pin "C") (pinfunction "C_C") (pintype "passive"))
      (node (ref "D50") (pin "A") (pinfunction "A_A") (pintype "passive"))
    )
    (net (code "110") (name "Net-(D50-PadC)") (class "Default")
      (node (ref "D50") (pin "C") (pinfunction "C_C") (pintype "passive"))
      (node (ref "D51") (pin "A") (pinfunction "A_A") (pintype "passive"))
    )
    (net (code "111") (name "Net-(D51-PadC)") (class "Default")
      (node (ref "D51") (pin "C") (pinfunction "C_C") (pintype "passive"))
      (node (ref "D52") (pin "A") (pinfunction "A_A") (pintype "passive"))
    )
    (net (code "112") (name "Net-(E2A-B)") (class "Default")
      (node (ref "E2") (pin "2") (pinfunction "B_2") (pintype "input"))
      (node (ref "E2") (pin "5") (pinfunction "Q_5") (pintype "output"))
    )
    (net (code "113") (name "Net-(E2A-C)") (class "Default")
      (node (ref "C27") (pin "1") (pinfunction "1_1") (pintype "passive"))
      (node (ref "E2") (pin "14") (pinfunction "C_14") (pintype "input"))
    )
    (net (code "114") (name "Net-(E2A-R{slash}C)") (class "Default")
      (node (ref "C27") (pin "2") (pinfunction "2_2") (pintype "passive"))
      (node (ref "E2") (pin "15") (pinfunction "R/C_15") (pintype "input"))
      (node (ref "R67") (pin "1") (pinfunction "1_1") (pintype "passive"))
    )
    (net (code "115") (name "Net-(E2A-~{Q})") (class "Default")
      (node (ref "E2") (pin "4") (pinfunction "~{Q}_4") (pintype "output"))
      (node (ref "E3") (pin "11") (pinfunction "CLR_11") (pintype "input"))
      (node (ref "E9") (pin "4") (pinfunction "PRE_4") (pintype "input"))
    )
    (net (code "116") (name "Net-(E2B-B)") (class "Default")
      (node (ref "E2") (pin "10") (pinfunction "B_10") (pintype "input"))
      (node (ref "E3") (pin "10") (pinfunction "B_10") (pintype "input"))
      (node (ref "E4") (pin "12") (pinfunction "~{Q}_12") (pintype "output"))
      (node (ref "E6") (pin "13") (pinfunction "CLR_13") (pintype "input"))
    )
    (net (code "117") (name "Net-(E2B-C)") (class "Default")
      (node (ref "C28") (pin "1") (pinfunction "1_1") (pintype "passive"))
      (node (ref "E2") (pin "6") (pinfunction "C_6") (pintype "input"))
    )
    (net (code "118") (name "Net-(E2B-R{slash}C)") (class "Default")
      (node (ref "C28") (pin "2") (pinfunction "2_2") (pintype "passive"))
      (node (ref "E2") (pin "7") (pinfunction "R/C_7") (pintype "input"))
      (node (ref "R66") (pin "1") (pinfunction "1_1") (pintype "passive"))
    )
    (net (code "119") (name "Net-(E3A-B)") (class "Default")
      (node (ref "E3") (pin "2") (pinfunction "B_2") (pintype "input"))
      (node (ref "E4") (pin "4") (pinfunction "~{Q}_4") (pintype "output"))
    )
    (net (code "120") (name "Net-(E3A-C)") (class "Default")
      (node (ref "C31") (pin "1") (pinfunction "1_1") (pintype "passive"))
      (node (ref "E3") (pin "14") (pinfunction "C_14") (pintype "input"))
    )
    (net (code "121") (name "Net-(E3A-R{slash}C)") (class "Default")
      (node (ref "C31") (pin "2") (pinfunction "2_2") (pintype "passive"))
      (node (ref "E3") (pin "15") (pinfunction "R/C_15") (pintype "input"))
      (node (ref "R65") (pin "1") (pinfunction "1_1") (pintype "passive"))
    )
    (net (code "122") (name "Net-(E3A-~{Q})") (class "Default")
      (node (ref "E3") (pin "4") (pinfunction "~{Q}_4") (pintype "output"))
      (node (ref "E4") (pin "9") (pinfunction "A_9") (pintype "input"))
      (node (ref "E9") (pin "10") (pinfunction "PRE_10") (pintype "input"))
    )
    (net (code "123") (name "Net-(E3B-C)") (class "Default")
      (node (ref "C26") (pin "1") (pinfunction "1_1") (pintype "passive"))
      (node (ref "E3") (pin "6") (pinfunction "C_6") (pintype "input"))
    )
    (net (code "124") (name "Net-(E3B-R{slash}C)") (class "Default")
      (node (ref "C26") (pin "2") (pinfunction "2_2") (pintype "passive"))
      (node (ref "E3") (pin "7") (pinfunction "R/C_7") (pintype "input"))
      (node (ref "R68") (pin "1") (pinfunction "1_1") (pintype "passive"))
    )
    (net (code "125") (name "Net-(E3B-~{Q})") (class "Default")
      (node (ref "E3") (pin "12") (pinfunction "~{Q}_12") (pintype "output"))
      (node (ref "E6") (pin "11") (pinfunction "CLK_11") (pintype "input"))
      (node (ref "E9") (pin "3") (pinfunction "CLK_3") (pintype "input"))
    )
    (net (code "126") (name "Net-(E4A-C)") (class "Default")
      (node (ref "C29") (pin "1") (pinfunction "1_1") (pintype "passive"))
      (node (ref "E4") (pin "14") (pinfunction "C_14") (pintype "input"))
    )
    (net (code "127") (name "Net-(E4A-R{slash}C)") (class "Default")
      (node (ref "C29") (pin "2") (pinfunction "2_2") (pintype "passive"))
      (node (ref "E4") (pin "15") (pinfunction "R/C_15") (pintype "input"))
      (node (ref "R79") (pin "1") (pinfunction "1_1") (pintype "passive"))
    )
    (net (code "128") (name "Net-(E4B-C)") (class "Default")
      (node (ref "C30") (pin "1") (pinfunction "1_1") (pintype "passive"))
      (node (ref "E4") (pin "6") (pinfunction "C_6") (pintype "input"))
    )
    (net (code "129") (name "Net-(E4B-R{slash}C)") (class "Default")
      (node (ref "C30") (pin "2") (pinfunction "2_2") (pintype "passive"))
      (node (ref "E4") (pin "7") (pinfunction "R/C_7") (pintype "input"))
      (node (ref "R80") (pin "1") (pinfunction "1_1") (pintype "passive"))
    )
    (net (code "130") (name "Net-(E7A-Q)") (class "Default")
      (node (ref "E7") (pin "5") (pinfunction "Q_5") (pintype "output"))
      (node (ref "E8") (pin "4") (pinfunction "I1_4") (pintype "input"))
    )
    (net (code "131") (name "Net-(E7B-~{Q})") (class "Default")
      (node (ref "E7") (pin "8") (pinfunction "~{Q}_8") (pintype "output"))
      (node (ref "E8") (pin "2") (pinfunction "I1_2") (pintype "input"))
    )
    (net (code "132") (name "Net-(E10A-O)") (class "Default")
      (node (ref "E10") (pin "3") (pinfunction "O_3") (pintype "output"))
      (node (ref "R69") (pin "1") (pinfunction "1_1") (pintype "passive"))
      (node (ref "R70") (pin "1") (pinfunction "1_1") (pintype "passive"))
    )
    (net (code "133") (name "Net-(E10B-O)") (class "Default")
      (node (ref "E10") (pin "2") (pinfunction "O_2") (pintype "output"))
      (node (ref "E6") (pin "1") (pinfunction "CLR_1") (pintype "input"))
      (node (ref "E7") (pin "1") (pinfunction "CLR_1") (pintype "input"))
      (node (ref "E7") (pin "13") (pinfunction "CLR_13") (pintype "input"))
    )
    (net (code "134") (name "Net-(E10D-I1)") (class "Default")
      (node (ref "E1") (pin "4") (pinfunction "O_4") (pintype "open_collector"))
      (node (ref "E10") (pin "12") (pinfunction "I1_12") (pintype "input"))
      (node (ref "R75") (pin "1") (pinfunction "1_1") (pintype "passive"))
    )
    (net (code "135") (name "Net-(E10D-O)") (class "Default")
      (node (ref "E10") (pin "13") (pinfunction "O_13") (pintype "output"))
      (node (ref "E28") (pin "12") (pinfunction "I1_12") (pintype "input"))
      (node (ref "E5") (pin "4") (pinfunction "I1_4") (pintype "input"))
    )
    (net (code "136") (name "Net-(E11A-I0)") (class "Default")
      (node (ref "E11") (pin "1") (pinfunction "I0_1") (pintype "input"))
      (node (ref "E20") (pin "13") (pinfunction "O_13") (pintype "output"))
      (node (ref "E22") (pin "13") (pinfunction "I_13") (pintype "input"))
    )
    (net (code "137") (name "Net-(E11A-I1)") (class "Default")
      (node (ref "E11") (pin "12") (pinfunction "I0_12") (pintype "input"))
      (node (ref "E11") (pin "2") (pinfunction "I1_2") (pintype "input"))
      (node (ref "E11") (pin "5") (pinfunction "I1_5") (pintype "input"))
      (node (ref "E15") (pin "14") (pinfunction "O_14") (pintype "output"))
    )
    (net (code "138") (name "Net-(E11A-O)") (class "Default")
      (node (ref "E11") (pin "3") (pinfunction "O_3") (pintype "output"))
      (node (ref "E7") (pin "10") (pinfunction "PRE_10") (pintype "input"))
    )
    (net (code "139") (name "Net-(E11B-I0)") (class "Default")
      (node (ref "E11") (pin "4") (pinfunction "I0_4") (pintype "input"))
      (node (ref "E13") (pin "1") (pinfunction "I_1") (pintype "input"))
      (node (ref "E20") (pin "3") (pinfunction "O_3") (pintype "output"))
    )
    (net (code "140") (name "Net-(E11B-O)") (class "Default")
      (node (ref "E11") (pin "6") (pinfunction "O_6") (pintype "output"))
      (node (ref "E6") (pin "4") (pinfunction "PRE_4") (pintype "input"))
    )
    (net (code "141") (name "Net-(E11C-I0)") (class "Default")
      (node (ref "E11") (pin "9") (pinfunction "I0_9") (pintype "input"))
      (node (ref "E6") (pin "5") (pinfunction "Q_5") (pintype "output"))
    )
    (net (code "142") (name "Net-(E11C-O)") (class "Default")
      (node (ref "E11") (pin "8") (pinfunction "O_8") (pintype "output"))
      (node (ref "E14") (pin "1") (pinfunction "I_1") (pintype "input"))
      (node (ref "E14") (pin "13") (pinfunction "I_13") (pintype "input"))
      (node (ref "E6") (pin "3") (pinfunction "CLK_3") (pintype "input"))
    )
    (net (code "143") (name "Net-(E11D-I1)") (class "Default")
      (node (ref "E11") (pin "13") (pinfunction "I1_13") (pintype "input"))
      (node (ref "E20") (pin "2") (pinfunction "O_2") (pintype "output"))
      (node (ref "E22") (pin "1") (pinfunction "I_1") (pintype "input"))
    )
    (net (code "144") (name "Net-(E11D-O)") (class "Default")
      (node (ref "E11") (pin "11") (pinfunction "O_11") (pintype "output"))
      (node (ref "E7") (pin "4") (pinfunction "PRE_4") (pintype "input"))
    )
    (net (code "145") (name "Net-(E12A-O)") (class "Default")
      (node (ref "E12") (pin "3") (pinfunction "O_3") (pintype "output"))
      (node (ref "E13") (pin "13") (pinfunction "I_13") (pintype "input"))
      (node (ref "E13") (pin "3") (pinfunction "I_3") (pintype "input"))
      (node (ref "E17") (pin "1") (pinfunction "I_1") (pintype "input"))
      (node (ref "E17") (pin "13") (pinfunction "I_13") (pintype "input"))
    )
    (net (code "146") (name "Net-(E12B-O)") (class "Default")
      (node (ref "E12") (pin "2") (pinfunction "O_2") (pintype "output"))
      (node (ref "E13") (pin "5") (pinfunction "I_5") (pintype "input"))
    )
    (net (code "147") (name "Net-(E12C-O)") (class "Default")
      (node (ref "E12") (pin "14") (pinfunction "O_14") (pintype "output"))
      (node (ref "E13") (pin "9") (pinfunction "I_9") (pintype "input"))
    )
    (net (code "148") (name "Net-(E12D-O)") (class "Default")
      (node (ref "E12") (pin "13") (pinfunction "O_13") (pintype "output"))
      (node (ref "E13") (pin "11") (pinfunction "I_11") (pintype "input"))
    )
    (net (code "149") (name "Net-(E14B-I)") (class "Default")
      (node (ref "E14") (pin "3") (pinfunction "I_3") (pintype "input"))
      (node (ref "E14") (pin "5") (pinfunction "I_5") (pintype "input"))
      (node (ref "E7") (pin "3") (pinfunction "CLK_3") (pintype "input"))
      (node (ref "E8") (pin "6") (pinfunction "O_6") (pintype "output"))
    )
    (net (code "150") (name "Net-(E14B-O)") (class "Default")
      (node (ref "D35") (pin "A") (pinfunction "A_A") (pintype "passive"))
      (node (ref "E14") (pin "4") (pinfunction "O_4") (pintype "open_collector"))
      (node (ref "Q2") (pin "2") (pinfunction "B_2") (pintype "passive"))
      (node (ref "R48") (pin "1") (pinfunction "1_1") (pintype "passive"))
    )
    (net (code "151") (name "Net-(E14D-I)") (class "Default")
      (node (ref "E14") (pin "11") (pinfunction "I_11") (pintype "input"))
      (node (ref "E14") (pin "9") (pinfunction "I_9") (pintype "input"))
      (node (ref "E24") (pin "8") (pinfunction "O_8") (pintype "output"))
      (node (ref "E7") (pin "11") (pinfunction "CLK_11") (pintype "input"))
    )
    (net (code "152") (name "Net-(E14D-O)") (class "Default")
      (node (ref "D31") (pin "A") (pinfunction "A_A") (pintype "passive"))
      (node (ref "E14") (pin "8") (pinfunction "O_8") (pintype "open_collector"))
      (node (ref "Q3") (pin "2") (pinfunction "B_2") (pintype "passive"))
      (node (ref "R51") (pin "1") (pinfunction "1_1") (pintype "passive"))
    )
    (net (code "153") (name "Net-(E14F-O)") (class "Default")
      (node (ref "D33") (pin "A") (pinfunction "A_A") (pintype "passive"))
      (node (ref "E14") (pin "12") (pinfunction "O_12") (pintype "open_collector"))
      (node (ref "Q1") (pin "2") (pinfunction "B_2") (pintype "passive"))
      (node (ref "R45") (pin "1") (pinfunction "1_1") (pintype "passive"))
    )
    (net (code "154") (name "Net-(E15D-O)") (class "Default")
      (node (ref "E15") (pin "13") (pinfunction "O_13") (pintype "output"))
      (node (ref "E5") (pin "5") (pinfunction "I2_5") (pintype "input"))
    )
    (net (code "155") (name "Net-(E16A-O)") (class "Default")
      (node (ref "E16") (pin "3") (pinfunction "O_3") (pintype "output"))
      (node (ref "E21") (pin "11") (pinfunction "I_11") (pintype "input"))
      (node (ref "E21") (pin "3") (pinfunction "I_3") (pintype "input"))
      (node (ref "E22") (pin "11") (pinfunction "I_11") (pintype "input"))
      (node (ref "E22") (pin "3") (pinfunction "I_3") (pintype "input"))
    )
    (net (code "156") (name "Net-(E16B-O)") (class "Default")
      (node (ref "E16") (pin "2") (pinfunction "O_2") (pintype "output"))
      (node (ref "E18") (pin "1") (pinfunction "I_1") (pintype "input"))
      (node (ref "E18") (pin "13") (pinfunction "I_13") (pintype "input"))
      (node (ref "E21") (pin "5") (pinfunction "I_5") (pintype "input"))
      (node (ref "E21") (pin "9") (pinfunction "I_9") (pintype "input"))
    )
    (net (code "157") (name "Net-(E16C-O)") (class "Default")
      (node (ref "E16") (pin "14") (pinfunction "O_14") (pintype "output"))
      (node (ref "E17") (pin "5") (pinfunction "I_5") (pintype "input"))
      (node (ref "E17") (pin "9") (pinfunction "I_9") (pintype "input"))
      (node (ref "E18") (pin "11") (pinfunction "I_11") (pintype "input"))
      (node (ref "E18") (pin "3") (pinfunction "I_3") (pintype "input"))
    )
    (net (code "158") (name "Net-(E16D-O)") (class "Default")
      (node (ref "E16") (pin "13") (pinfunction "O_13") (pintype "output"))
      (node (ref "E17") (pin "11") (pinfunction "I_11") (pintype "input"))
      (node (ref "E17") (pin "3") (pinfunction "I_3") (pintype "input"))
      (node (ref "E18") (pin "5") (pinfunction "I_5") (pintype "input"))
      (node (ref "E18") (pin "9") (pinfunction "I_9") (pintype "input"))
    )
    (net (code "159") (name "Net-(E19A-CLK)") (class "Default")
      (node (ref "E19") (pin "3") (pinfunction "CLK_3") (pintype "input"))
      (node (ref "E9") (pin "8") (pinfunction "~{Q}_8") (pintype "output"))
    )
    (net (code "160") (name "Net-(E19A-CLR)") (class "Default")
      (node (ref "E19") (pin "1") (pinfunction "CLR_1") (pintype "input"))
      (node (ref "E19") (pin "13") (pinfunction "CLR_13") (pintype "input"))
      (node (ref "E4") (pin "3") (pinfunction "CLR_3") (pintype "input"))
      (node (ref "E5") (pin "6") (pinfunction "O_6") (pintype "output"))
    )
    (net (code "161") (name "Net-(E19A-D)") (class "Default")
      (node (ref "E19") (pin "11") (pinfunction "CLK_11") (pintype "input"))
      (node (ref "E19") (pin "2") (pinfunction "D_2") (pintype "input"))
      (node (ref "E19") (pin "6") (pinfunction "~{Q}_6") (pintype "output"))
    )
    (net (code "162") (name "Net-(E19A-PRE)") (class "Default")
      (node (ref "E19") (pin "10") (pinfunction "PRE_10") (pintype "input"))
      (node (ref "E19") (pin "4") (pinfunction "PRE_4") (pintype "input"))
      (node (ref "E9") (pin "13") (pinfunction "CLR_13") (pintype "input"))
      (node (ref "R72") (pin "1") (pinfunction "1_1") (pintype "passive"))
      (node (ref "R73") (pin "2") (pinfunction "2_2") (pintype "passive"))
    )
    (net (code "163") (name "Net-(E19A-Q)") (class "Default")
      (node (ref "E19") (pin "5") (pinfunction "Q_5") (pintype "output"))
      (node (ref "E28") (pin "3") (pinfunction "I1_3") (pintype "input"))
      (node (ref "U$2") (pin "CA1") (pinfunction "1_CA1") (pintype "bidirectional"))
    )
    (net (code "164") (name "Net-(E19B-D)") (class "Default")
      (node (ref "E19") (pin "12") (pinfunction "D_12") (pintype "input"))
      (node (ref "E19") (pin "8") (pinfunction "~{Q}_8") (pintype "output"))
    )
    (net (code "165") (name "Net-(E19B-Q)") (class "Default")
      (node (ref "E19") (pin "9") (pinfunction "Q_9") (pintype "output"))
      (node (ref "E28") (pin "6") (pinfunction "I1_6") (pintype "input"))
      (node (ref "U$2") (pin "DA1") (pinfunction "1_DA1") (pintype "bidirectional"))
    )
    (net (code "166") (name "Net-(E20C-O)") (class "Default")
      (node (ref "E20") (pin "14") (pinfunction "O_14") (pintype "output"))
      (node (ref "E21") (pin "1") (pinfunction "I_1") (pintype "input"))
      (node (ref "E21") (pin "13") (pinfunction "I_13") (pintype "input"))
      (node (ref "E22") (pin "5") (pinfunction "I_5") (pintype "input"))
      (node (ref "E22") (pin "9") (pinfunction "I_9") (pintype "input"))
    )
    (net (code "167") (name "Net-(E24A-O)") (class "Default")
      (node (ref "E24") (pin "6") (pinfunction "O_6") (pintype "output"))
      (node (ref "E29") (pin "2") (pinfunction "I0_2") (pintype "input"))
    )
    (net (code "168") (name "Net-(E24B-I1)") (class "Default")
      (node (ref "E24") (pin "10") (pinfunction "I1_10") (pintype "input"))
      (node (ref "E7") (pin "9") (pinfunction "Q_9") (pintype "output"))
    )
    (net (code "169") (name "Net-(E24B-I2)") (class "Default")
      (node (ref "E24") (pin "12") (pinfunction "I2_12") (pintype "input"))
      (node (ref "E6") (pin "6") (pinfunction "~{Q}_6") (pintype "output"))
      (node (ref "E8") (pin "5") (pinfunction "I2_5") (pintype "input"))
    )
    (net (code "170") (name "Net-(E24B-I3)") (class "Default")
      (node (ref "E24") (pin "13") (pinfunction "I3_13") (pintype "input"))
      (node (ref "E7") (pin "6") (pinfunction "~{Q}_6") (pintype "output"))
      (node (ref "E8") (pin "1") (pinfunction "I0_1") (pintype "input"))
    )
    (net (code "171") (name "Net-(E25D-I1)") (class "Default")
      (node (ref "E25") (pin "12") (pinfunction "I1_12") (pintype "input"))
      (node (ref "E26") (pin "12") (pinfunction "O_12") (pintype "output"))
    )
    (net (code "172") (name "Net-(E26A-I)") (class "Default")
      (node (ref "E26") (pin "1") (pinfunction "I_1") (pintype "input"))
      (node (ref "E30") (pin "2") (pinfunction "O_2") (pintype "output"))
    )
    (net (code "173") (name "Net-(E26A-O)") (class "Default")
      (node (ref "E26") (pin "2") (pinfunction "O_2") (pintype "output"))
      (node (ref "E27") (pin "3") (pinfunction "I_3") (pintype "input"))
      (node (ref "E27") (pin "5") (pinfunction "I_5") (pintype "input"))
    )
    (net (code "174") (name "Net-(E26B-O)") (class "Default")
      (node (ref "E26") (pin "4") (pinfunction "O_4") (pintype "output"))
      (node (ref "E28") (pin "8") (pinfunction "I0_8") (pintype "input"))
      (node (ref "E28") (pin "9") (pinfunction "I1_9") (pintype "input"))
    )
    (net (code "175") (name "Net-(E26C-O)") (class "Default")
      (node (ref "E26") (pin "10") (pinfunction "O_10") (pintype "output"))
      (node (ref "E26") (pin "6") (pinfunction "O_6") (pintype "output"))
      (node (ref "E29") (pin "11") (pinfunction "I0_11") (pintype "input"))
      (node (ref "E29") (pin "6") (pinfunction "I1_6") (pintype "input"))
    )
    (net (code "176") (name "Net-(E27A-I)") (class "Default")
      (node (ref "E27") (pin "1") (pinfunction "I_1") (pintype "input"))
      (node (ref "E27") (pin "13") (pinfunction "I_13") (pintype "input"))
      (node (ref "E30") (pin "14") (pinfunction "O_14") (pintype "output"))
    )
    (net (code "177") (name "Net-(E27B-O)") (class "Default")
      (node (ref "D43") (pin "A") (pinfunction "A_A") (pintype "passive"))
      (node (ref "E27") (pin "4") (pinfunction "O_4") (pintype "open_collector"))
      (node (ref "Q6") (pin "2") (pinfunction "B_2") (pintype "passive"))
      (node (ref "R60") (pin "1") (pinfunction "1_1") (pintype "passive"))
    )
    (net (code "178") (name "Net-(E27D-I)") (class "Default")
      (node (ref "E27") (pin "11") (pinfunction "I_11") (pintype "input"))
      (node (ref "E27") (pin "9") (pinfunction "I_9") (pintype "input"))
      (node (ref "E30") (pin "13") (pinfunction "O_13") (pintype "output"))
    )
    (net (code "179") (name "Net-(E27D-O)") (class "Default")
      (node (ref "D37") (pin "A") (pinfunction "A_A") (pintype "passive"))
      (node (ref "E27") (pin "8") (pinfunction "O_8") (pintype "open_collector"))
      (node (ref "Q4") (pin "2") (pinfunction "B_2") (pintype "passive"))
      (node (ref "R54") (pin "1") (pinfunction "1_1") (pintype "passive"))
    )
    (net (code "180") (name "Net-(E27F-O)") (class "Default")
      (node (ref "D41") (pin "A") (pinfunction "A_A") (pintype "passive"))
      (node (ref "E27") (pin "12") (pinfunction "O_12") (pintype "open_collector"))
      (node (ref "Q5") (pin "2") (pinfunction "B_2") (pintype "passive"))
      (node (ref "R57") (pin "1") (pinfunction "1_1") (pintype "passive"))
    )
    (net (code "181") (name "Net-(E29A-I1)") (class "Default")
      (node (ref "E29") (pin "3") (pinfunction "I1_3") (pintype "input"))
      (node (ref "E39") (pin "8") (pinfunction "O_8") (pintype "output"))
    )
    (net (code "182") (name "Net-(E31A-I0)") (class "Default")
      (node (ref "E31") (pin "2") (pinfunction "I0_2") (pintype "input"))
      (node (ref "E38") (pin "4") (pinfunction "O_4") (pintype "output"))
    )
    (net (code "183") (name "Net-(E31B-I0)") (class "Default")
      (node (ref "E31") (pin "5") (pinfunction "I0_5") (pintype "input"))
      (node (ref "E41") (pin "8") (pinfunction "O_8") (pintype "output"))
    )
    (net (code "184") (name "Net-(E31C-I1)") (class "Default")
      (node (ref "E31") (pin "9") (pinfunction "I1_9") (pintype "input"))
      (node (ref "E38") (pin "12") (pinfunction "O_12") (pintype "output"))
    )
    (net (code "185") (name "Net-(E31D-I1)") (class "Default")
      (node (ref "E31") (pin "12") (pinfunction "I1_12") (pintype "input"))
      (node (ref "E38") (pin "8") (pinfunction "O_8") (pintype "output"))
    )
    (net (code "186") (name "Net-(E32A-O)") (class "Default")
      (node (ref "E32") (pin "3") (pinfunction "O_3") (pintype "output"))
      (node (ref "E36") (pin "9") (pinfunction "I_9") (pintype "input"))
    )
    (net (code "187") (name "Net-(E32B-O)") (class "Default")
      (node (ref "E32") (pin "2") (pinfunction "O_2") (pintype "output"))
      (node (ref "E33") (pin "3") (pinfunction "I_3") (pintype "input"))
    )
    (net (code "188") (name "Net-(E32C-O)") (class "Default")
      (node (ref "E32") (pin "14") (pinfunction "O_14") (pintype "output"))
      (node (ref "E33") (pin "9") (pinfunction "I_9") (pintype "input"))
    )
    (net (code "189") (name "Net-(E32D-O)") (class "Default")
      (node (ref "E32") (pin "13") (pinfunction "O_13") (pintype "output"))
      (node (ref "E33") (pin "13") (pinfunction "I_13") (pintype "input"))
    )
    (net (code "190") (name "Net-(E33A-I)") (class "Default")
      (node (ref "E33") (pin "1") (pinfunction "I_1") (pintype "input"))
      (node (ref "E37") (pin "14") (pinfunction "O_14") (pintype "output"))
    )
    (net (code "191") (name "Net-(E33C-I)") (class "Default")
      (node (ref "E33") (pin "5") (pinfunction "I_5") (pintype "input"))
      (node (ref "E37") (pin "13") (pinfunction "O_13") (pintype "output"))
    )
    (net (code "192") (name "Net-(E33E-I)") (class "Default")
      (node (ref "E33") (pin "11") (pinfunction "I_11") (pintype "input"))
      (node (ref "E37") (pin "2") (pinfunction "O_2") (pintype "output"))
    )
    (net (code "193") (name "Net-(E34A-I0)") (class "Default")
      (node (ref "E34") (pin "2") (pinfunction "I0_2") (pintype "input"))
      (node (ref "E41") (pin "4") (pinfunction "O_4") (pintype "output"))
    )
    (net (code "194") (name "Net-(E34B-I0)") (class "Default")
      (node (ref "E34") (pin "5") (pinfunction "I0_5") (pintype "input"))
      (node (ref "E41") (pin "2") (pinfunction "O_2") (pintype "output"))
    )
    (net (code "195") (name "Net-(E34C-I1)") (class "Default")
      (node (ref "E34") (pin "9") (pinfunction "I1_9") (pintype "input"))
      (node (ref "E41") (pin "12") (pinfunction "O_12") (pintype "output"))
    )
    (net (code "196") (name "Net-(E34D-I1)") (class "Default")
      (node (ref "E34") (pin "12") (pinfunction "I1_12") (pintype "input"))
      (node (ref "E41") (pin "10") (pinfunction "O_10") (pintype "output"))
    )
    (net (code "197") (name "Net-(E35A-O)") (class "Default")
      (node (ref "E35") (pin "3") (pinfunction "O_3") (pintype "output"))
      (node (ref "E36") (pin "3") (pinfunction "I_3") (pintype "input"))
    )
    (net (code "198") (name "Net-(E35B-O)") (class "Default")
      (node (ref "E35") (pin "2") (pinfunction "O_2") (pintype "output"))
      (node (ref "E36") (pin "5") (pinfunction "I_5") (pintype "input"))
    )
    (net (code "199") (name "Net-(E35C-O)") (class "Default")
      (node (ref "E35") (pin "14") (pinfunction "O_14") (pintype "output"))
      (node (ref "E36") (pin "11") (pinfunction "I_11") (pintype "input"))
    )
    (net (code "200") (name "Net-(E35D-O)") (class "Default")
      (node (ref "E35") (pin "13") (pinfunction "O_13") (pintype "output"))
      (node (ref "E36") (pin "13") (pinfunction "I_13") (pintype "input"))
    )
    (net (code "201") (name "Net-(E36A-I)") (class "Default")
      (node (ref "E36") (pin "1") (pinfunction "I_1") (pintype "input"))
      (node (ref "E37") (pin "3") (pinfunction "O_3") (pintype "output"))
    )
    (net (code "202") (name "Net-(E38A-O)") (class "Default")
      (node (ref "E38") (pin "2") (pinfunction "O_2") (pintype "output"))
      (node (ref "E40") (pin "6") (pinfunction "I1_6") (pintype "input"))
    )
    (net (code "203") (name "Net-(E38C-O)") (class "Default")
      (node (ref "E38") (pin "6") (pinfunction "O_6") (pintype "output"))
      (node (ref "E40") (pin "2") (pinfunction "I0_2") (pintype "input"))
    )
    (net (code "204") (name "Net-(E38E-O)") (class "Default")
      (node (ref "E38") (pin "10") (pinfunction "O_10") (pintype "output"))
      (node (ref "E40") (pin "8") (pinfunction "I0_8") (pintype "input"))
    )
    (net (code "205") (name "Net-(E40D-I1)") (class "Default")
      (node (ref "E40") (pin "12") (pinfunction "I1_12") (pintype "input"))
      (node (ref "E41") (pin "6") (pinfunction "O_6") (pintype "output"))
    )
    (net (code "206") (name "Net-(Q1-C)") (class "Default")
      (node (ref "C24") (pin "1") (pinfunction "1_1") (pintype "passive"))
      (node (ref "Q1") (pin "3") (pinfunction "C_3") (pintype "passive"))
      (node (ref "R44") (pin "1") (pinfunction "1_1") (pintype "passive"))
    )
    (net (code "207") (name "Net-(Q2-C)") (class "Default")
      (node (ref "C23") (pin "1") (pinfunction "1_1") (pintype "passive"))
      (node (ref "Q2") (pin "3") (pinfunction "C_3") (pintype "passive"))
      (node (ref "R47") (pin "1") (pinfunction "1_1") (pintype "passive"))
    )
    (net (code "208") (name "Net-(Q3-C)") (class "Default")
      (node (ref "C25") (pin "1") (pinfunction "1_1") (pintype "passive"))
      (node (ref "Q3") (pin "3") (pinfunction "C_3") (pintype "passive"))
      (node (ref "R50") (pin "1") (pinfunction "1_1") (pintype "passive"))
    )
    (net (code "209") (name "Net-(Q4-C)") (class "Default")
      (node (ref "Q4") (pin "3") (pinfunction "C_3") (pintype "passive"))
      (node (ref "R53") (pin "1") (pinfunction "1_1") (pintype "passive"))
    )
    (net (code "210") (name "Net-(Q5-C)") (class "Default")
      (node (ref "Q5") (pin "3") (pinfunction "C_3") (pintype "passive"))
      (node (ref "R56") (pin "1") (pinfunction "1_1") (pintype "passive"))
    )
    (net (code "211") (name "Net-(Q6-C)") (class "Default")
      (node (ref "Q6") (pin "3") (pinfunction "C_3") (pintype "passive"))
      (node (ref "R59") (pin "1") (pinfunction "1_1") (pintype "passive"))
    )
    (net (code "212") (name "Net-(Q7-B)") (class "Default")
      (node (ref "Q7") (pin "2") (pinfunction "B_2") (pintype "passive"))
      (node (ref "R69") (pin "2") (pinfunction "2_2") (pintype "passive"))
    )
    (net (code "213") (name "Net-(R45-Pad2)") (class "Default")
      (node (ref "R45") (pin "2") (pinfunction "2_2") (pintype "passive"))
      (node (ref "R46") (pin "1") (pinfunction "1_1") (pintype "passive"))
    )
    (net (code "214") (name "Net-(R48-Pad2)") (class "Default")
      (node (ref "R48") (pin "2") (pinfunction "2_2") (pintype "passive"))
      (node (ref "R49") (pin "1") (pinfunction "1_1") (pintype "passive"))
    )
    (net (code "215") (name "Net-(R51-Pad2)") (class "Default")
      (node (ref "R51") (pin "2") (pinfunction "2_2") (pintype "passive"))
      (node (ref "R52") (pin "1") (pinfunction "1_1") (pintype "passive"))
    )
    (net (code "216") (name "Net-(R54-Pad2)") (class "Default")
      (node (ref "R54") (pin "2") (pinfunction "2_2") (pintype "passive"))
      (node (ref "R55") (pin "1") (pinfunction "1_1") (pintype "passive"))
    )
    (net (code "217") (name "Net-(R57-Pad2)") (class "Default")
      (node (ref "R57") (pin "2") (pinfunction "2_2") (pintype "passive"))
      (node (ref "R58") (pin "1") (pinfunction "1_1") (pintype "passive"))
    )
    (net (code "218") (name "Net-(R60-Pad2)") (class "Default")
      (node (ref "R60") (pin "2") (pinfunction "2_2") (pintype "passive"))
      (node (ref "R61") (pin "1") (pinfunction "1_1") (pintype "passive"))
    )
    (net (code "219") (name "Net-(R70-Pad2)") (class "Default")
      (node (ref "R70") (pin "2") (pinfunction "2_2") (pintype "passive"))
      (node (ref "R71") (pin "1") (pinfunction "1_1") (pintype "passive"))
    )
    (net (code "220") (name "Net-(R73-Pad1)") (class "Default")
      (node (ref "R73") (pin "1") (pinfunction "1_1") (pintype "passive"))
      (node (ref "R74") (pin "2") (pinfunction "2_2") (pintype "passive"))
    )
    (net (code "221") (name "Net-(R75-Pad2)") (class "Default")
      (node (ref "R75") (pin "2") (pinfunction "2_2") (pintype "passive"))
      (node (ref "R78") (pin "1") (pinfunction "1_1") (pintype "passive"))
    )
    (net (code "222") (name "Net-(R81-E)") (class "Default")
      (node (ref "R79") (pin "2") (pinfunction "2_2") (pintype "passive"))
      (node (ref "R81") (pin "3") (pinfunction "E_3") (pintype "passive"))
      (node (ref "R83") (pin "1") (pinfunction "1_1") (pintype "passive"))
    )
    (net (code "223") (name "Net-(R82-E)") (class "Default")
      (node (ref "R80") (pin "2") (pinfunction "2_2") (pintype "passive"))
      (node (ref "R82") (pin "3") (pinfunction "E_3") (pintype "passive"))
      (node (ref "R84") (pin "1") (pinfunction "1_1") (pintype "passive"))
    )
    (net (code "224") (name "VCC") (class "Default")
      (node (ref "C1") (pin "1") (pinfunction "1_1") (pintype "passive"))
      (node (ref "C10") (pin "1") (pinfunction "1_1") (pintype "passive"))
      (node (ref "C11") (pin "1") (pinfunction "1_1") (pintype "passive"))
      (node (ref "C12") (pin "1") (pinfunction "1_1") (pintype "passive"))
      (node (ref "C13") (pin "1") (pinfunction "1_1") (pintype "passive"))
      (node (ref "C14") (pin "1") (pinfunction "1_1") (pintype "passive"))
      (node (ref "C15") (pin "1") (pinfunction "1_1") (pintype "passive"))
      (node (ref "C16") (pin "1") (pinfunction "1_1") (pintype "passive"))
      (node (ref "C17") (pin "1") (pinfunction "1_1") (pintype "passive"))
      (node (ref "C18") (pin "1") (pinfunction "1_1") (pintype "passive"))
      (node (ref "C19") (pin "1") (pinfunction "1_1") (pintype "passive"))
      (node (ref "C2") (pin "1") (pinfunction "1_1") (pintype "passive"))
      (node (ref "C20") (pin "+") (pinfunction "+_+") (pintype "passive"))
      (node (ref "C21") (pin "+") (pinfunction "+_+") (pintype "passive"))
      (node (ref "C22") (pin "+") (pinfunction "+_+") (pintype "passive"))
      (node (ref "C3") (pin "1") (pinfunction "1_1") (pintype "passive"))
      (node (ref "C32") (pin "1") (pinfunction "1_1") (pintype "passive"))
      (node (ref "C4") (pin "1") (pinfunction "1_1") (pintype "passive"))
      (node (ref "C5") (pin "1") (pinfunction "1_1") (pintype "passive"))
      (node (ref "C6") (pin "1") (pinfunction "1_1") (pintype "passive"))
      (node (ref "C7") (pin "1") (pinfunction "1_1") (pintype "passive"))
      (node (ref "C8") (pin "1") (pinfunction "1_1") (pintype "passive"))
      (node (ref "C9") (pin "1") (pinfunction "1_1") (pintype "passive"))
      (node (ref "R1") (pin "2") (pinfunction "2_2") (pintype "passive"))
      (node (ref "R10") (pin "2") (pinfunction "2_2") (pintype "passive"))
      (node (ref "R11") (pin "2") (pinfunction "2_2") (pintype "passive"))
      (node (ref "R12") (pin "2") (pinfunction "2_2") (pintype "passive"))
      (node (ref "R13") (pin "2") (pinfunction "2_2") (pintype "passive"))
      (node (ref "R14") (pin "2") (pinfunction "2_2") (pintype "passive"))
      (node (ref "R15") (pin "2") (pinfunction "2_2") (pintype "passive"))
      (node (ref "R16") (pin "2") (pinfunction "2_2") (pintype "passive"))
      (node (ref "R17") (pin "2") (pinfunction "2_2") (pintype "passive"))
      (node (ref "R18") (pin "2") (pinfunction "2_2") (pintype "passive"))
      (node (ref "R19") (pin "2") (pinfunction "2_2") (pintype "passive"))
      (node (ref "R2") (pin "2") (pinfunction "2_2") (pintype "passive"))
      (node (ref "R20") (pin "2") (pinfunction "2_2") (pintype "passive"))
      (node (ref "R21") (pin "2") (pinfunction "2_2") (pintype "passive"))
      (node (ref "R22") (pin "2") (pinfunction "2_2") (pintype "passive"))
      (node (ref "R23") (pin "2") (pinfunction "2_2") (pintype "passive"))
      (node (ref "R24") (pin "2") (pinfunction "2_2") (pintype "passive"))
      (node (ref "R25") (pin "2") (pinfunction "2_2") (pintype "passive"))
      (node (ref "R26") (pin "2") (pinfunction "2_2") (pintype "passive"))
      (node (ref "R27") (pin "2") (pinfunction "2_2") (pintype "passive"))
      (node (ref "R28") (pin "2") (pinfunction "2_2") (pintype "passive"))
      (node (ref "R29") (pin "2") (pinfunction "2_2") (pintype "passive"))
      (node (ref "R3") (pin "2") (pinfunction "2_2") (pintype "passive"))
      (node (ref "R30") (pin "2") (pinfunction "2_2") (pintype "passive"))
      (node (ref "R31") (pin "2") (pinfunction "2_2") (pintype "passive"))
      (node (ref "R32") (pin "2") (pinfunction "2_2") (pintype "passive"))
      (node (ref "R33") (pin "2") (pinfunction "2_2") (pintype "passive"))
      (node (ref "R34") (pin "2") (pinfunction "2_2") (pintype "passive"))
      (node (ref "R35") (pin "2") (pinfunction "2_2") (pintype "passive"))
      (node (ref "R36") (pin "2") (pinfunction "2_2") (pintype "passive"))
      (node (ref "R37") (pin "2") (pinfunction "2_2") (pintype "passive"))
      (node (ref "R38") (pin "2") (pinfunction "2_2") (pintype "passive"))
      (node (ref "R39") (pin "2") (pinfunction "2_2") (pintype "passive"))
      (node (ref "R4") (pin "2") (pinfunction "2_2") (pintype "passive"))
      (node (ref "R40") (pin "2") (pinfunction "2_2") (pintype "passive"))
      (node (ref "R41") (pin "2") (pinfunction "2_2") (pintype "passive"))
      (node (ref "R42") (pin "2") (pinfunction "2_2") (pintype "passive"))
      (node (ref "R43") (pin "2") (pinfunction "2_2") (pintype "passive"))
      (node (ref "R44") (pin "2") (pinfunction "2_2") (pintype "passive"))
      (node (ref "R46") (pin "2") (pinfunction "2_2") (pintype "passive"))
      (node (ref "R47") (pin "2") (pinfunction "2_2") (pintype "passive"))
      (node (ref "R49") (pin "2") (pinfunction "2_2") (pintype "passive"))
      (node (ref "R5") (pin "2") (pinfunction "2_2") (pintype "passive"))
      (node (ref "R50") (pin "2") (pinfunction "2_2") (pintype "passive"))
      (node (ref "R52") (pin "2") (pinfunction "2_2") (pintype "passive"))
      (node (ref "R53") (pin "2") (pinfunction "2_2") (pintype "passive"))
      (node (ref "R55") (pin "2") (pinfunction "2_2") (pintype "passive"))
      (node (ref "R56") (pin "2") (pinfunction "2_2") (pintype "passive"))
      (node (ref "R58") (pin "2") (pinfunction "2_2") (pintype "passive"))
      (node (ref "R59") (pin "2") (pinfunction "2_2") (pintype "passive"))
      (node (ref "R6") (pin "2") (pinfunction "2_2") (pintype "passive"))
      (node (ref "R61") (pin "2") (pinfunction "2_2") (pintype "passive"))
      (node (ref "R62") (pin "2") (pinfunction "2_2") (pintype "passive"))
      (node (ref "R63") (pin "2") (pinfunction "2_2") (pintype "passive"))
      (node (ref "R64") (pin "2") (pinfunction "2_2") (pintype "passive"))
      (node (ref "R65") (pin "2") (pinfunction "2_2") (pintype "passive"))
      (node (ref "R66") (pin "2") (pinfunction "2_2") (pintype "passive"))
      (node (ref "R67") (pin "2") (pinfunction "2_2") (pintype "passive"))
      (node (ref "R68") (pin "2") (pinfunction "2_2") (pintype "passive"))
      (node (ref "R7") (pin "2") (pinfunction "2_2") (pintype "passive"))
      (node (ref "R71") (pin "2") (pinfunction "2_2") (pintype "passive"))
      (node (ref "R72") (pin "2") (pinfunction "2_2") (pintype "passive"))
      (node (ref "R76") (pin "2") (pinfunction "2_2") (pintype "passive"))
      (node (ref "R77") (pin "2") (pinfunction "2_2") (pintype "passive"))
      (node (ref "R78") (pin "2") (pinfunction "2_2") (pintype "passive"))
      (node (ref "R8") (pin "2") (pinfunction "2_2") (pintype "passive"))
      (node (ref "R81") (pin "1") (pinfunction "A_1") (pintype "passive"))
      (node (ref "R81") (pin "2") (pinfunction "S_2") (pintype "passive"))
      (node (ref "R82") (pin "1") (pinfunction "A_1") (pintype "passive"))
      (node (ref "R82") (pin "2") (pinfunction "S_2") (pintype "passive"))
      (node (ref "R83") (pin "2") (pinfunction "2_2") (pintype "passive"))
      (node (ref "R84") (pin "2") (pinfunction "2_2") (pintype "passive"))
      (node (ref "R9") (pin "2") (pinfunction "2_2") (pintype "passive"))
      (node (ref "U$2") (pin "AA2") (pinfunction "1_AA2") (pintype "bidirectional"))
      (node (ref "U$2") (pin "BA2") (pinfunction "1_BA2") (pintype "bidirectional"))
      (node (ref "U$2") (pin "CA2") (pinfunction "1_CA2") (pintype "bidirectional"))
    )
    (net (code "225") (name "unconnected-(E2A-Q-Pad13)") (class "Default")
      (node (ref "E2") (pin "13") (pinfunction "Q_13") (pintype "output"))
    )
    (net (code "226") (name "unconnected-(E2B-~{Q}-Pad12)") (class "Default")
      (node (ref "E2") (pin "12") (pinfunction "~{Q}_12") (pintype "output"))
    )
    (net (code "227") (name "unconnected-(E3A-Q-Pad13)") (class "Default")
      (node (ref "E3") (pin "13") (pinfunction "Q_13") (pintype "output"))
    )
    (net (code "228") (name "unconnected-(E4A-Q-Pad13)") (class "Default")
      (node (ref "E4") (pin "13") (pinfunction "Q_13") (pintype "output"))
    )
    (net (code "229") (name "unconnected-(E4B-Q-Pad5)") (class "Default")
      (node (ref "E4") (pin "5") (pinfunction "Q_5") (pintype "output"))
    )
    (net (code "230") (name "unconnected-(E9A-Q-Pad5)") (class "Default")
      (node (ref "E9") (pin "5") (pinfunction "Q_5") (pintype "output"))
    )
    (net (code "231") (name "unconnected-(E9B-Q-Pad9)") (class "Default")
      (node (ref "E9") (pin "9") (pinfunction "Q_9") (pintype "output"))
    )
  )
)
